# rev_n_v31.net
KiCad netlist of a schematic drawn in EAGLE
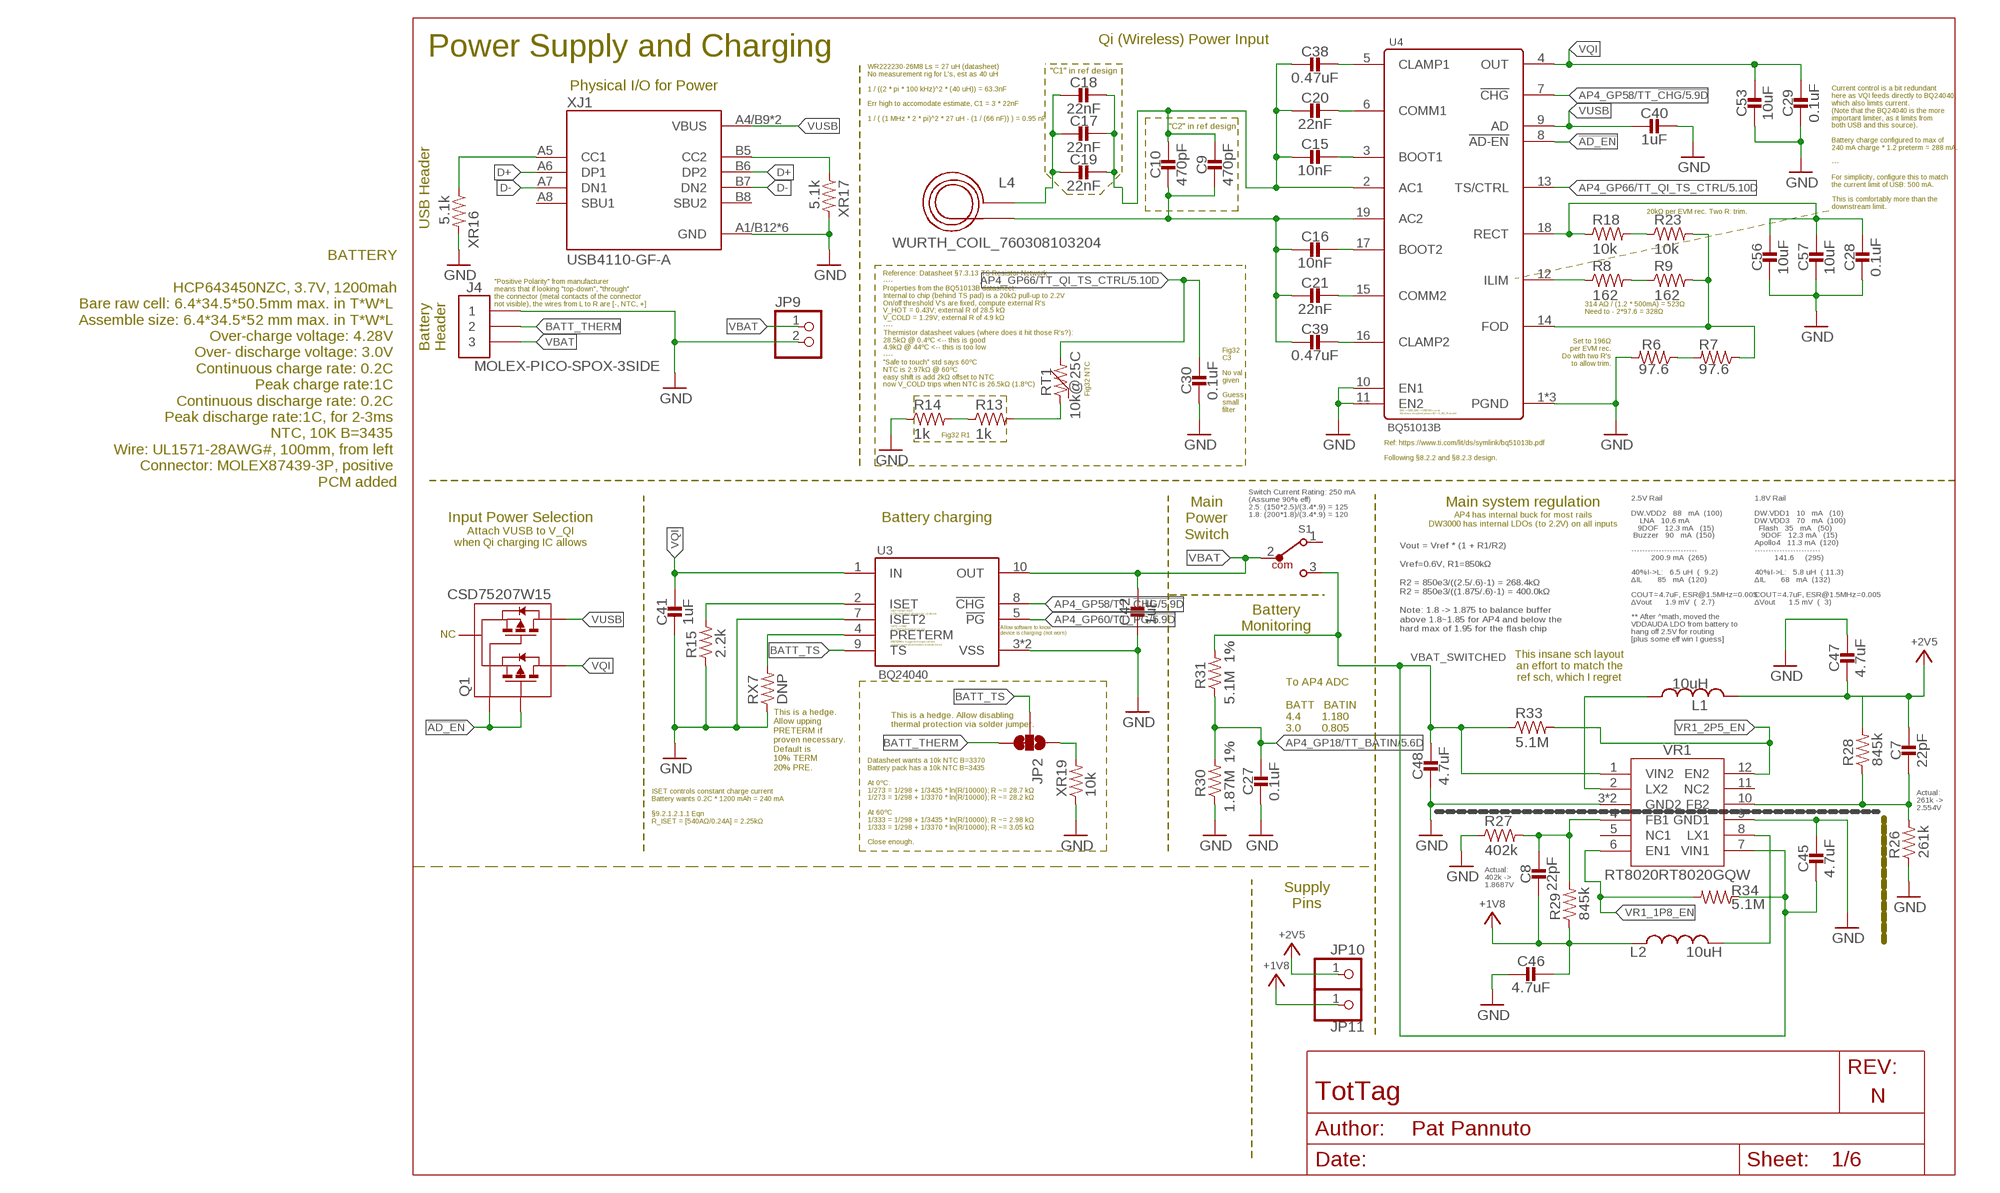
[diagram p0: schematic, sheet 1]
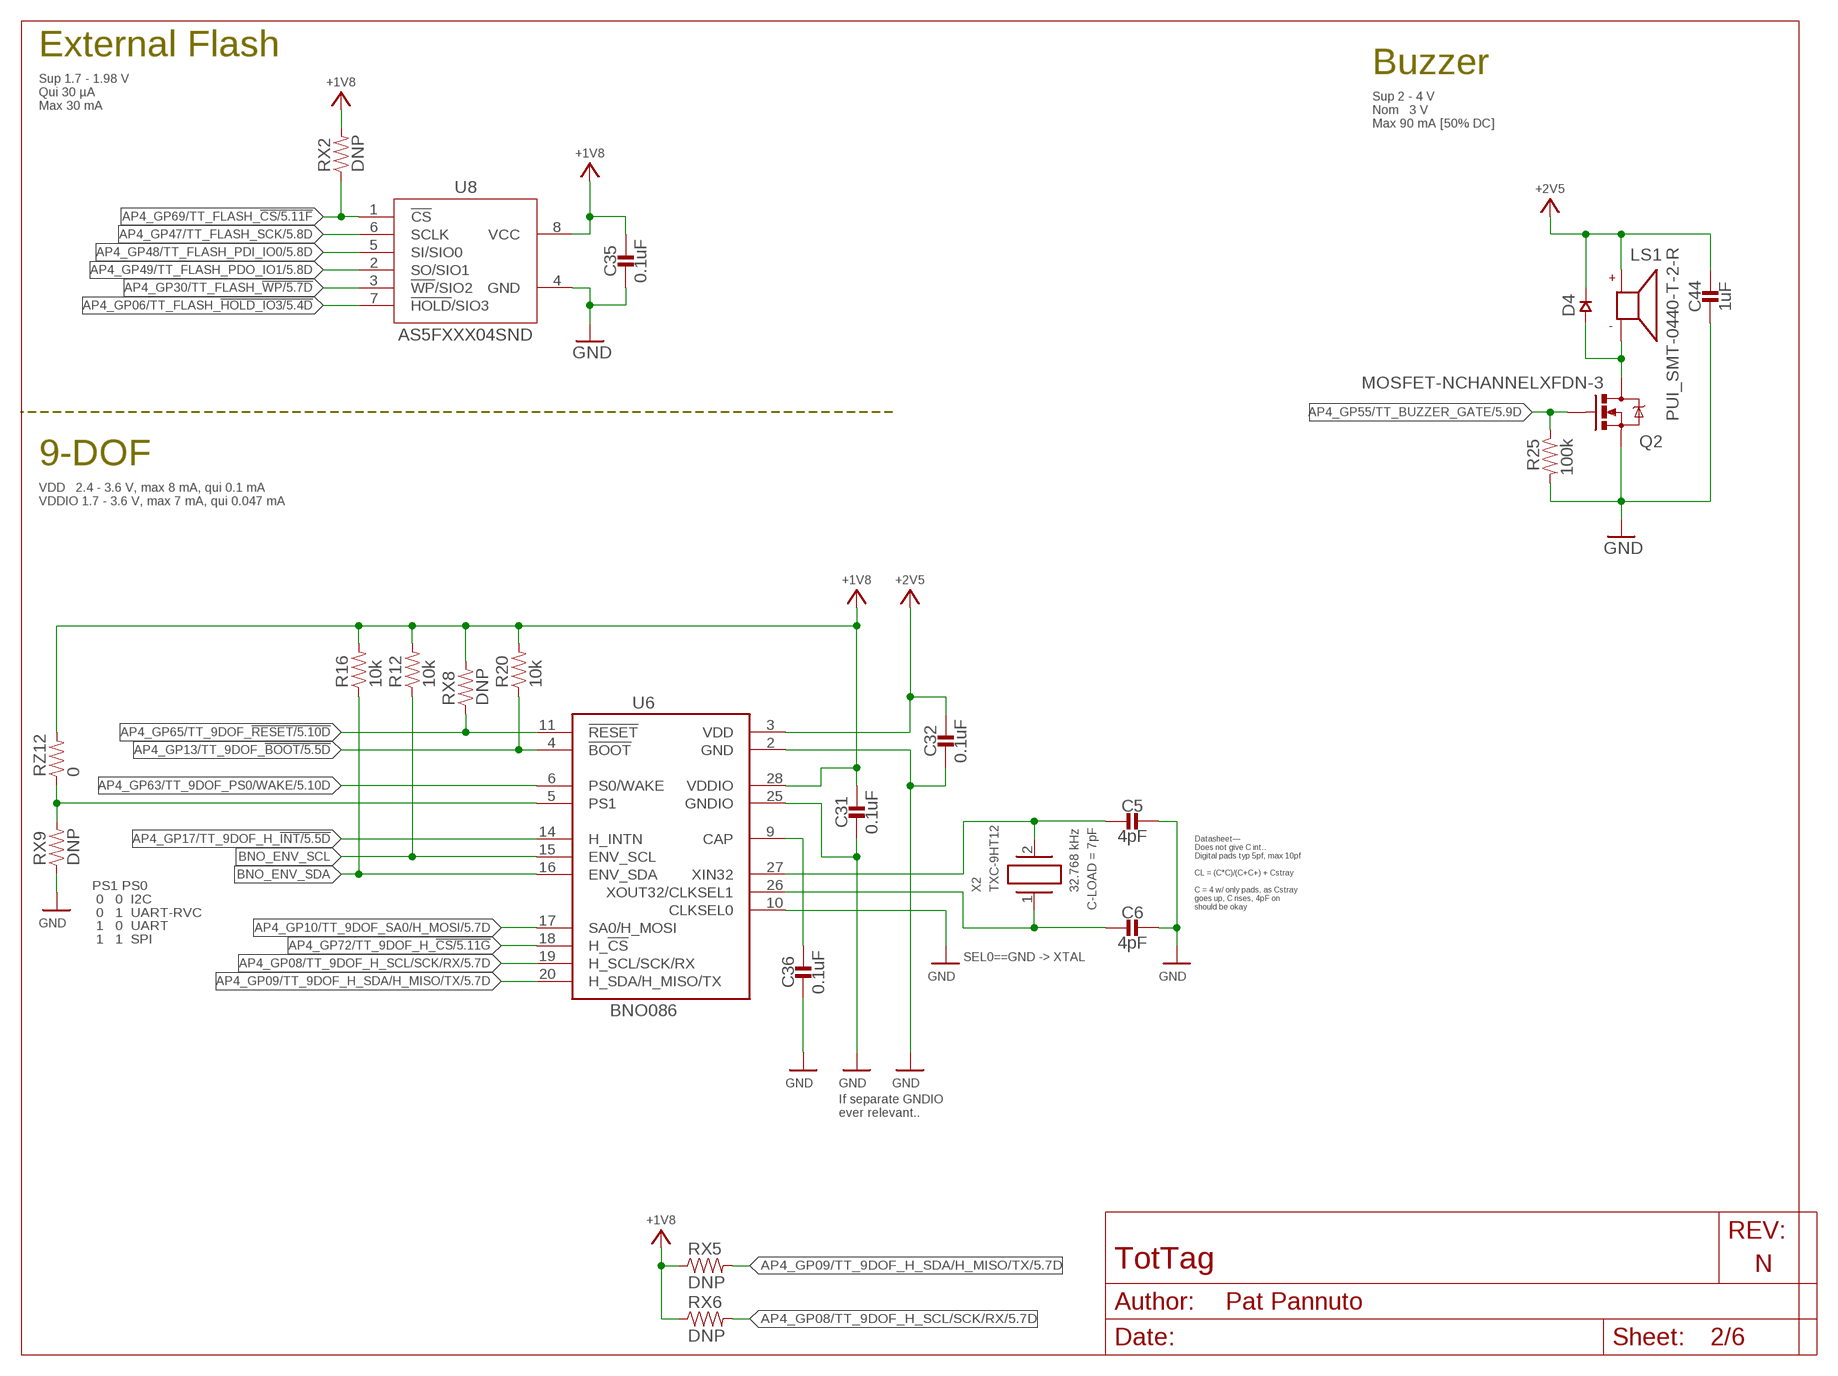
[diagram p1: schematic, sheet 2]
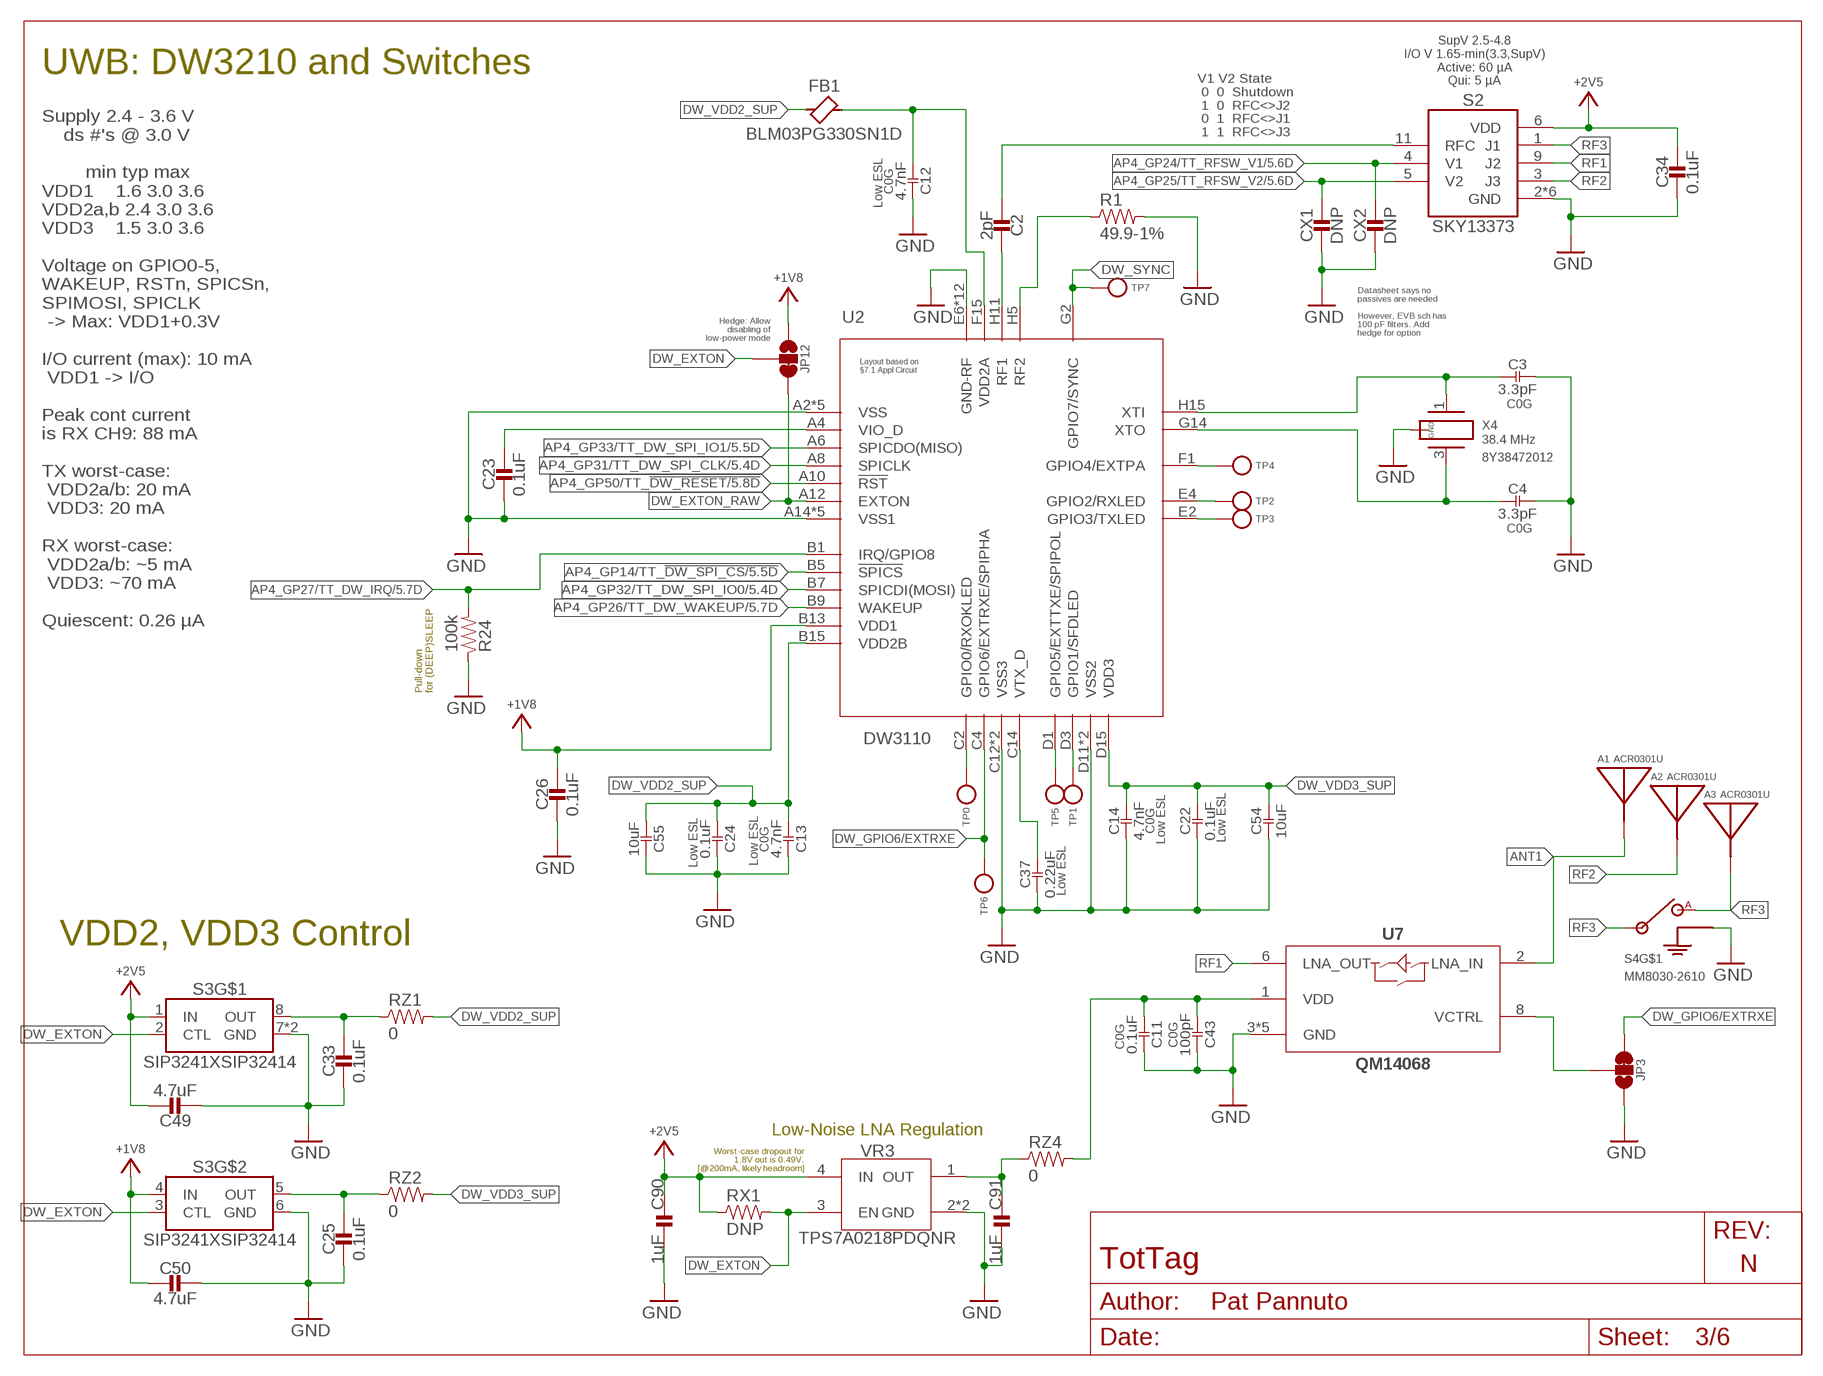
[diagram p2: schematic, sheet 3]
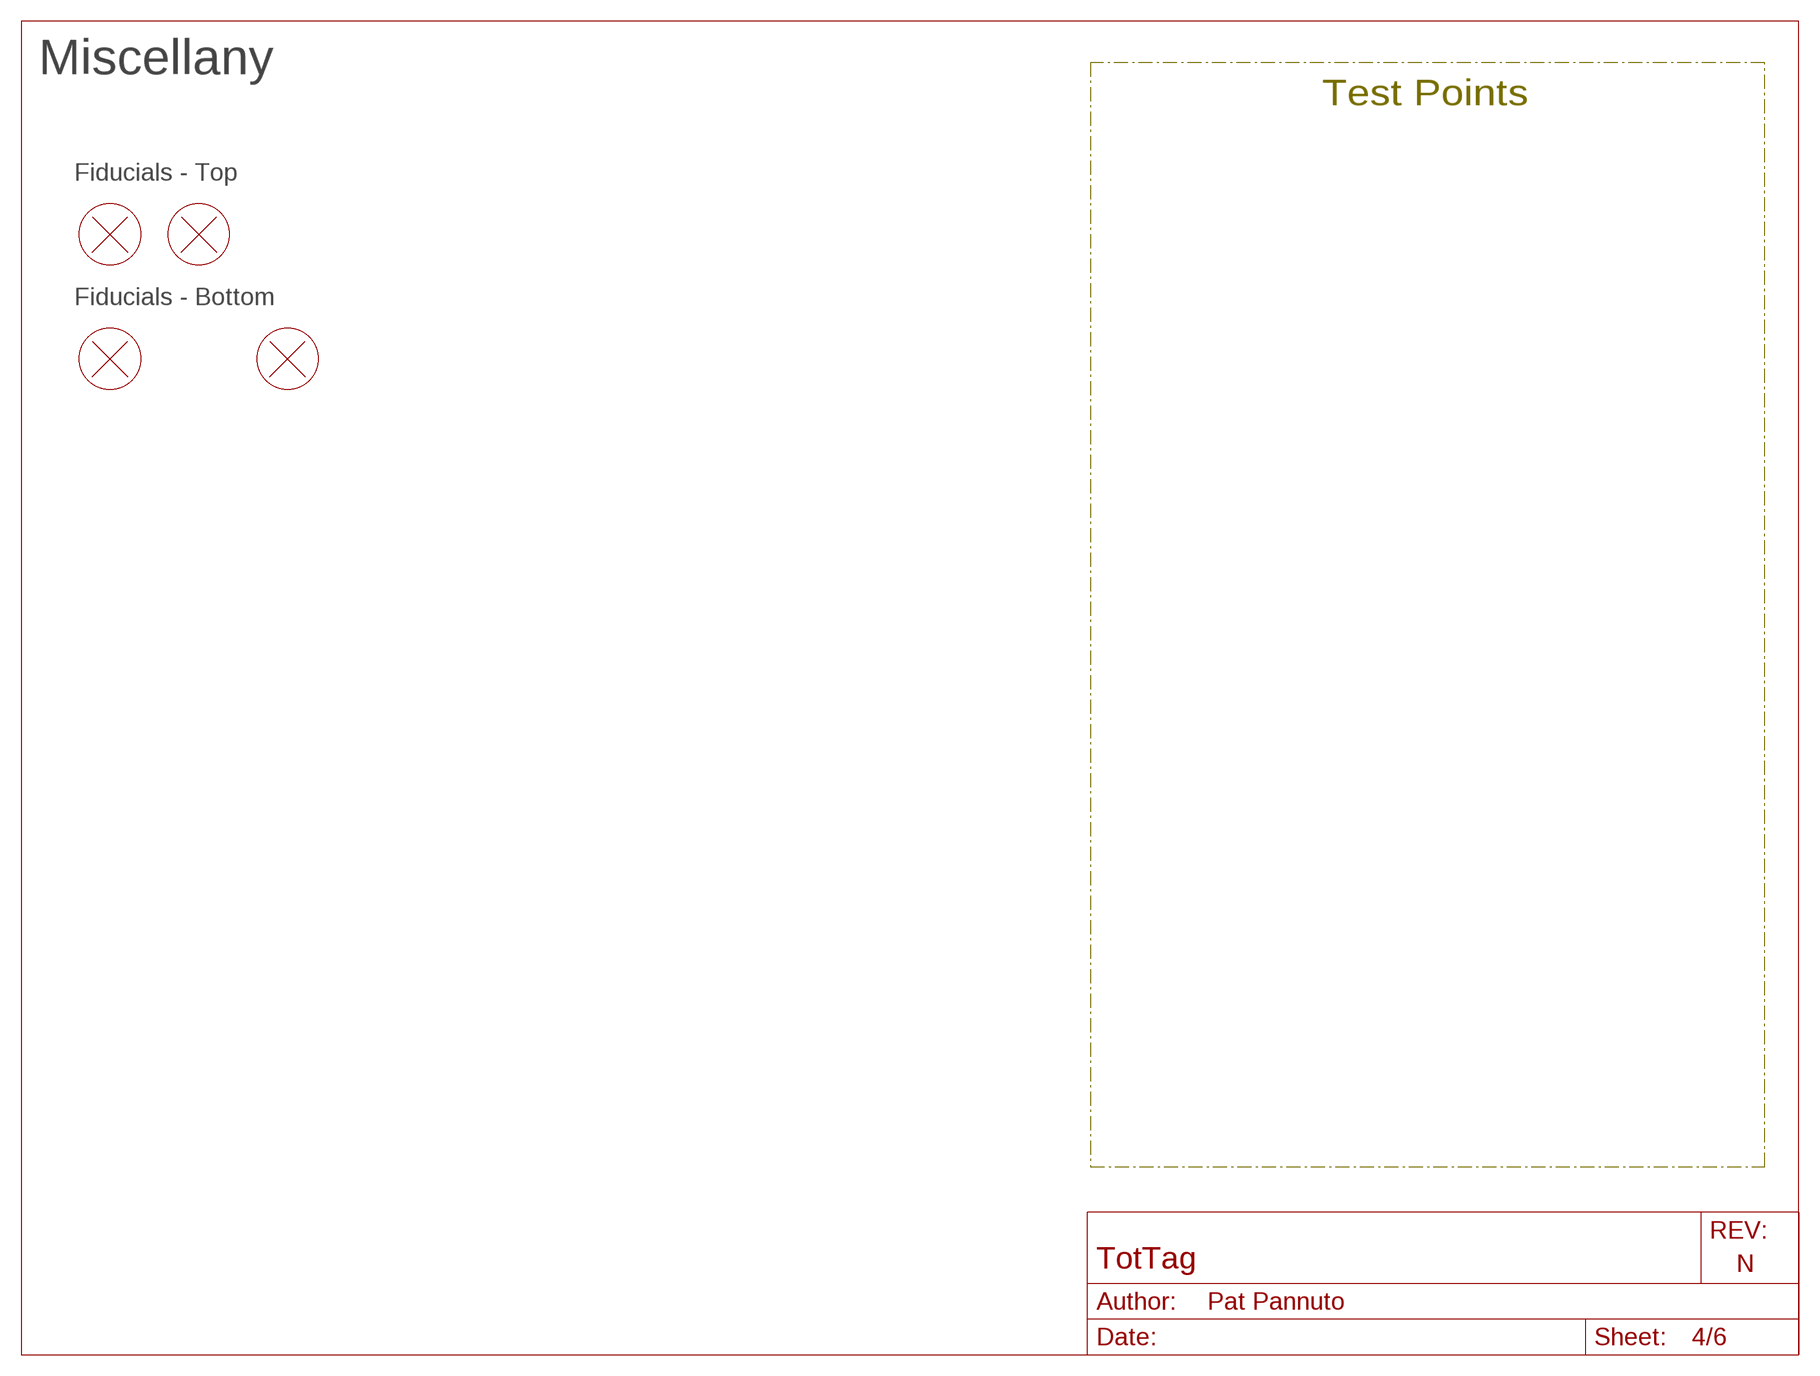
[diagram p3: schematic, sheet 4]
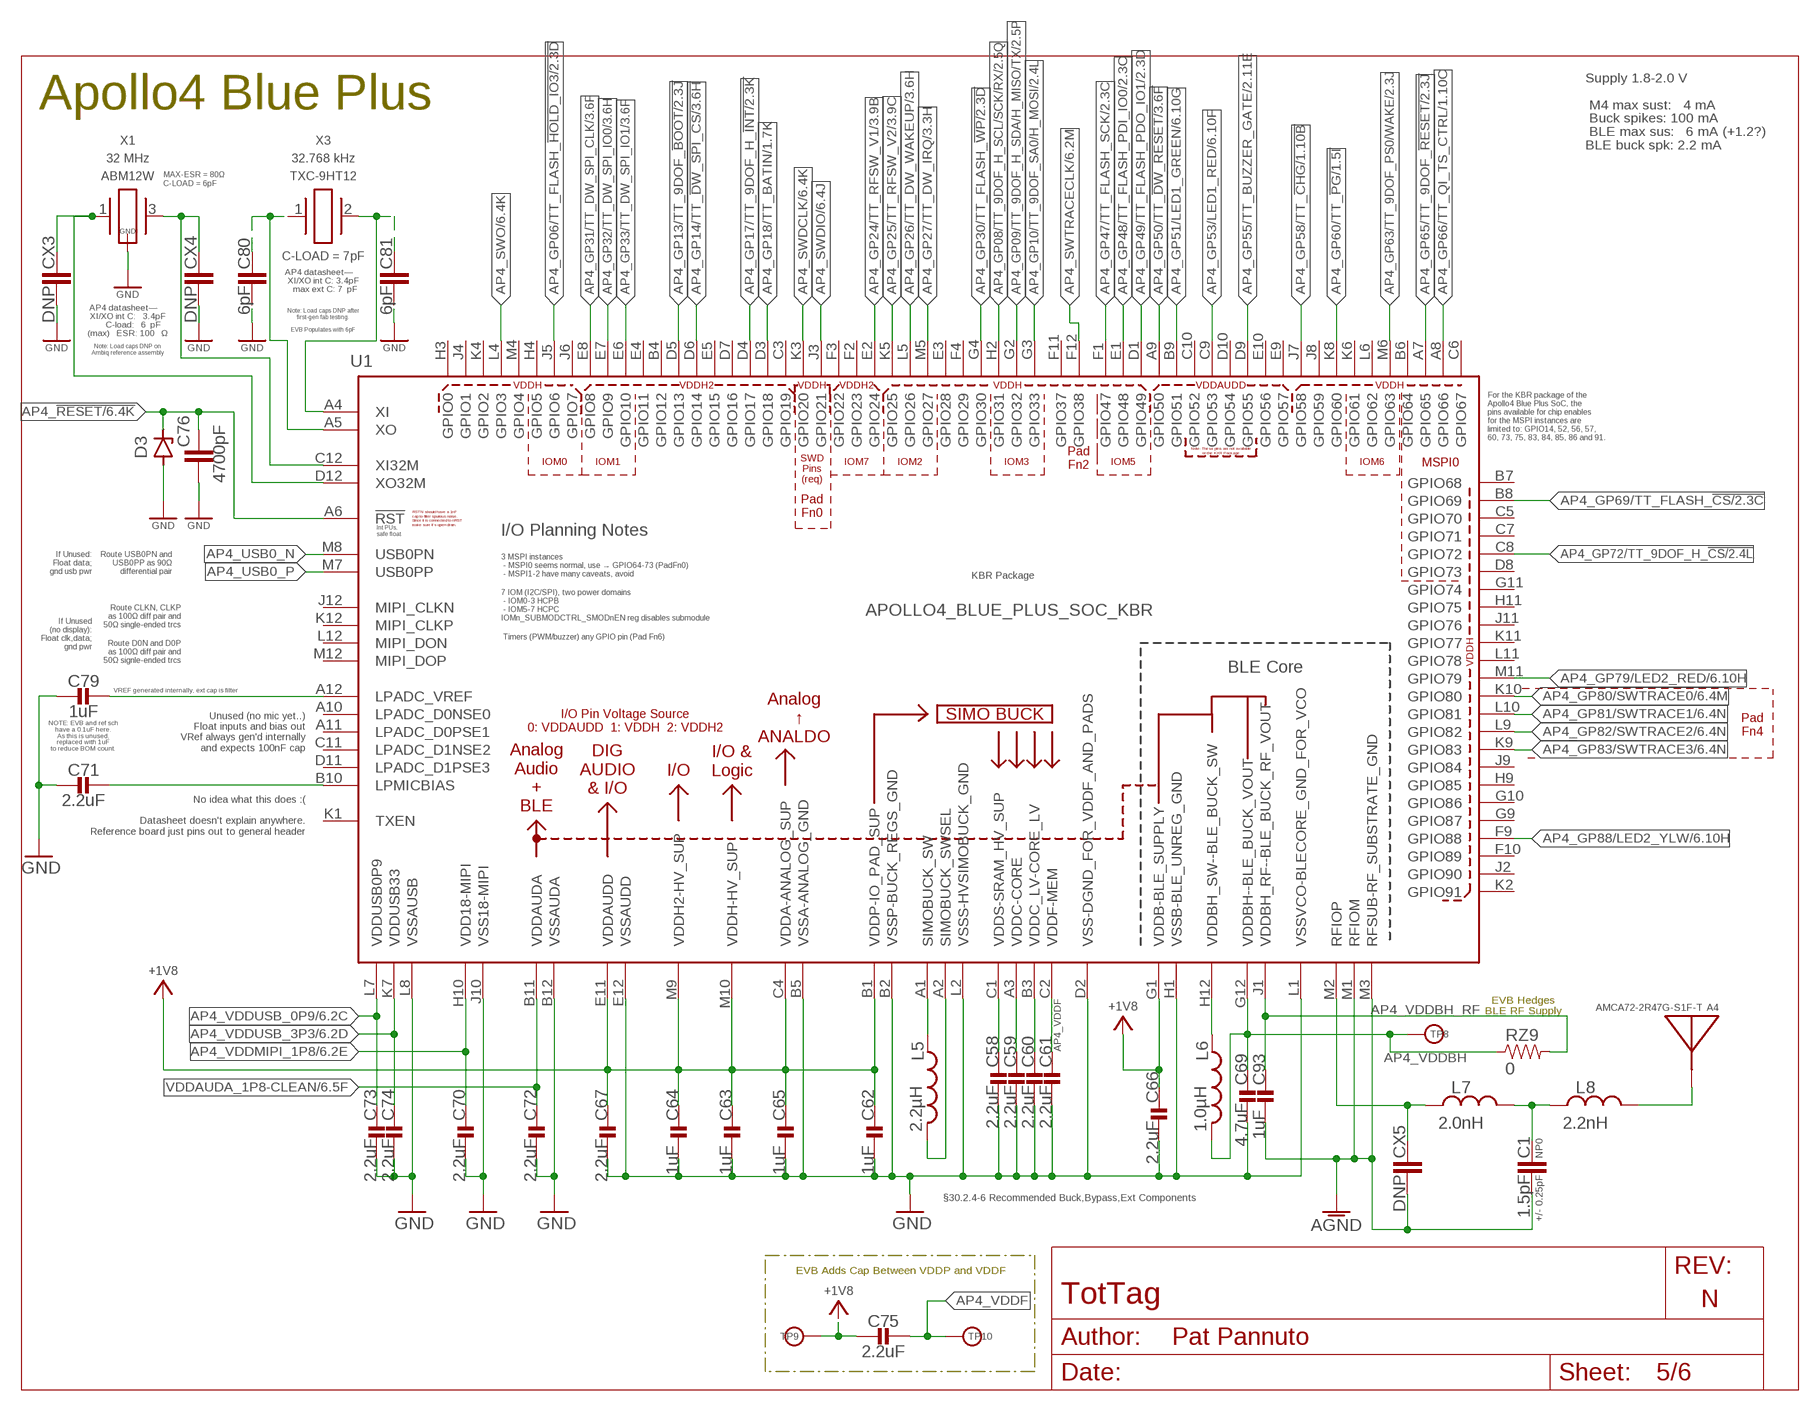
[diagram p4: schematic, sheet 5]
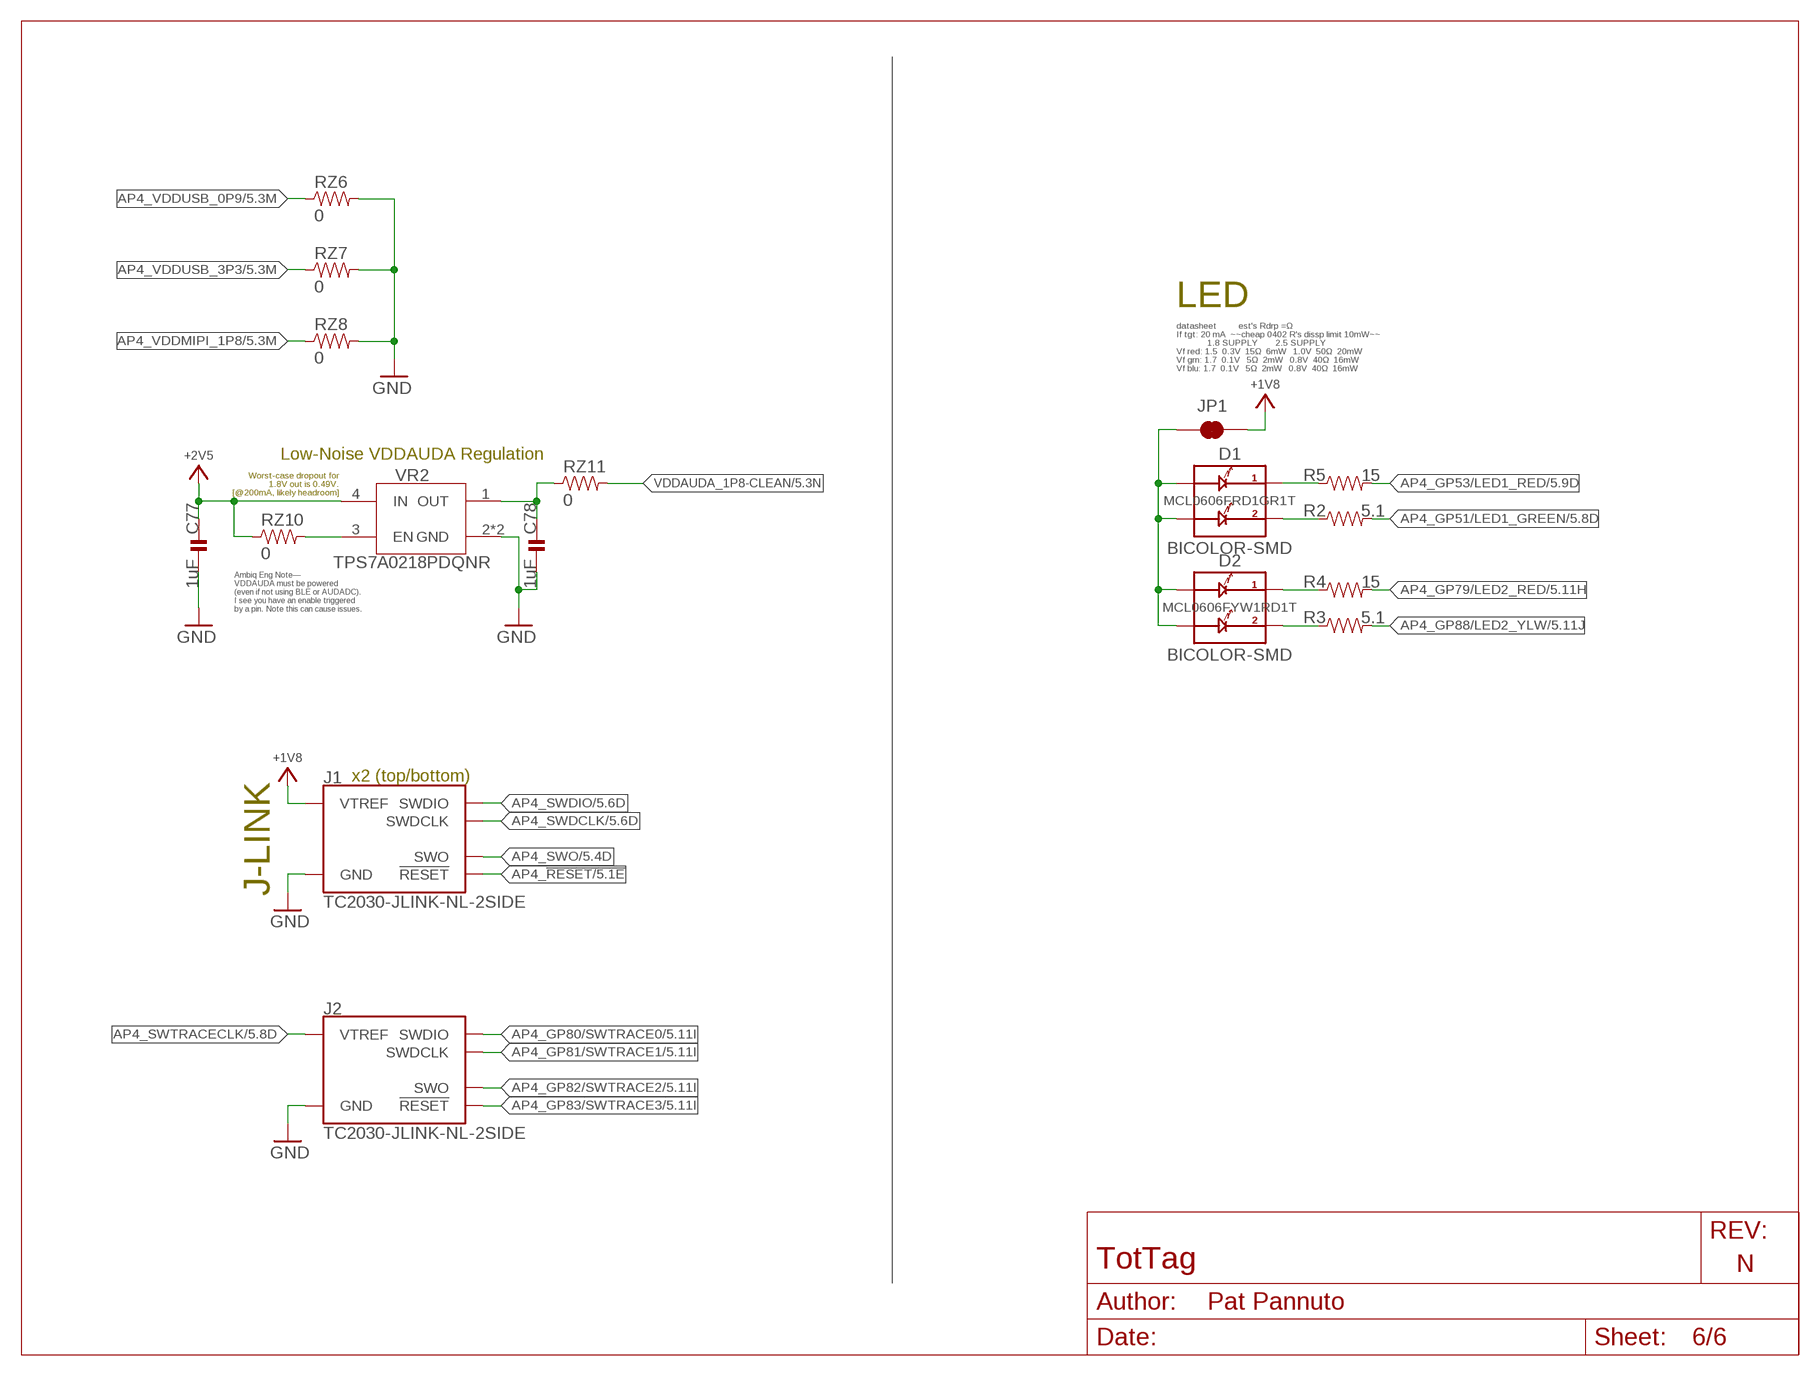
[diagram p5: schematic, sheet 6]

(export (version "E")
  (design (tool "Eeschema 10.0.6"))
  (components
    (comp (ref "A1")
      (value "ACR0301U")
      (footprint "eagle-import:ACR0301U")
      (fields (field (name "MANUFACTURER") "Abracon"))
      (libsource (lib "eagle-import") (part "ACR0301U"))
    )
    (comp (ref "A2")
      (value "ACR0301U")
      (footprint "eagle-import:ACR0301U")
      (fields (field (name "MANUFACTURER") "Abracon"))
      (libsource (lib "eagle-import") (part "ACR0301U"))
    )
    (comp (ref "A3")
      (value "ACR0301U")
      (footprint "eagle-import:ACR0301U")
      (fields (field (name "MANUFACTURER") "Abracon"))
      (libsource (lib "eagle-import") (part "ACR0301U"))
    )
    (comp (ref "C2")
      (value "2pF")
      (footprint "eagle-import:0201_CAP")
      (fields (field (name "MPN") "CBR02C209A5GAC"))
      (libsource (lib "eagle-import") (part "CAPACITOR0201_CAP"))
    )
    (comp (ref "C3")
      (value "3.3pF")
      (footprint "eagle-import:SMD_2012M-0805US-C")
      (fields
        (field (name "EIA") "C0G")
        (field (name "MANUFACTURER") "KYOCERA AVX")
        (field (name "MPN") "600F3R3BT250XT")
      )
      (libsource (lib "eagle-import") (part "C0805US"))
    )
    (comp (ref "C4")
      (value "3.3pF")
      (footprint "eagle-import:SMD_2012M-0805US-C")
      (fields
        (field (name "EIA") "C0G")
        (field (name "MANUFACTURER") "KYOCERA AVX")
        (field (name "MPN") "600F3R3BT250XT")
      )
      (libsource (lib "eagle-import") (part "C0805US"))
    )
    (comp (ref "C11")
      (value "0.1uF")
      (footprint "eagle-import:SMD_3216M-1206US-C")
      (fields (field (name "EIA") "C0G") (field (name "MPN") "GRM31C5C1H104JA01L"))
      (libsource (lib "eagle-import") (part "C1206US"))
    )
    (comp (ref "C12")
      (value "4.7nF")
      (footprint "eagle-import:SMD_1608M-0603US-C")
      (fields
        (field (name "EIA") "C0G")
        (field (name "FEATURES") "Low ESL")
        (field (name "MANUFACTURER") "KEMET")
        (field (name "MPN") "C0603C472J5GAC7867")
      )
      (libsource (lib "eagle-import") (part "C0603US"))
    )
    (comp (ref "C13")
      (value "4.7nF")
      (footprint "eagle-import:SMD_1608M-0603US-C")
      (fields
        (field (name "EIA") "C0G")
        (field (name "FEATURES") "Low ESL")
        (field (name "MANUFACTURER") "KEMET")
        (field (name "MPN") "C0603C472J5GAC7867")
      )
      (libsource (lib "eagle-import") (part "C0603US"))
    )
    (comp (ref "C14")
      (value "4.7nF")
      (footprint "eagle-import:SMD_1608M-0603US-C")
      (fields
        (field (name "EIA") "C0G")
        (field (name "FEATURES") "Low ESL")
        (field (name "MANUFACTURER") "KEMET")
        (field (name "MPN") "C0603C472J5GAC7867")
      )
      (libsource (lib "eagle-import") (part "C0603US"))
    )
    (comp (ref "C22")
      (value "0.1uF")
      (footprint "eagle-import:SMD_1608M-0603US-C")
      (fields (field (name "FEATURES") "Low ESL") (field (name "MPN") "C1608X7R1H104K080AA"))
      (libsource (lib "eagle-import") (part "C0603US"))
    )
    (comp (ref "C23")
      (value "0.1uF")
      (footprint "eagle-import:0402_CAP")
      (fields (field (name "MPN") "CL05A104KP5NNNC"))
      (libsource (lib "eagle-import") (part "passives_20904581_CAPACITOR0402_CAP"))
    )
    (comp (ref "C24")
      (value "0.1uF")
      (footprint "eagle-import:SMD_1608M-0603US-C")
      (fields (field (name "FEATURES") "Low ESL") (field (name "MPN") "C1608X7R1H104K080AA"))
      (libsource (lib "eagle-import") (part "C0603US"))
    )
    (comp (ref "C25")
      (value "0.1uF")
      (footprint "eagle-import:0402_CAP")
      (fields (field (name "MPN") "CL05A104KP5NNNC"))
      (libsource (lib "eagle-import") (part "passives_20904581_CAPACITOR0402_CAP"))
    )
    (comp (ref "C26")
      (value "0.1uF")
      (footprint "eagle-import:0402_CAP")
      (fields (field (name "MPN") "CL05A104KP5NNNC"))
      (libsource (lib "eagle-import") (part "passives_20904581_CAPACITOR0402_CAP"))
    )
    (comp (ref "C33")
      (value "0.1uF")
      (footprint "eagle-import:0402_CAP")
      (fields (field (name "MPN") "CL05A104KP5NNNC"))
      (libsource (lib "eagle-import") (part "passives_20904581_CAPACITOR0402_CAP"))
    )
    (comp (ref "C34")
      (value "0.1uF")
      (footprint "eagle-import:0402_CAP")
      (fields (field (name "MPN") "CL05A104KP5NNNC"))
      (libsource (lib "eagle-import") (part "passives_20904581_CAPACITOR0402_CAP"))
    )
    (comp (ref "C37")
      (value "0.22uF")
      (footprint "eagle-import:SMD_1608M-0603US-C")
      (fields (field (name "FEATURES") "Low ESL") (field (name "MPN") "C1608X7R1H224K080AB"))
      (libsource (lib "eagle-import") (part "C0603US"))
    )
    (comp (ref "C43")
      (value "100pF")
      (footprint "eagle-import:SMD_1005M-0402US-C")
      (fields (field (name "EIA") "C0G") (field (name "MPN") "C0402C101J3GACTU"))
      (libsource (lib "eagle-import") (part "C0402US"))
    )
    (comp (ref "C49")
      (value "4.7uF")
      (footprint "eagle-import:0603_CAP")
      (fields (field (name "MPN") "C1608X7S1A475K080AC"))
      (libsource (lib "eagle-import") (part "passives_20904581_CAPACITOR0603_CAP"))
    )
    (comp (ref "C50")
      (value "4.7uF")
      (footprint "eagle-import:0603_CAP")
      (fields (field (name "MPN") "C1608X7S1A475K080AC"))
      (libsource (lib "eagle-import") (part "passives_20904581_CAPACITOR0603_CAP"))
    )
    (comp (ref "C54")
      (value "10uF")
      (footprint "eagle-import:SMD_1608M-0603US-C")
      (fields (field (name "MPN") "CM105X5R106M25AT"))
      (libsource (lib "eagle-import") (part "C0603US"))
    )
    (comp (ref "C55")
      (value "10uF")
      (footprint "eagle-import:SMD_1608M-0603US-C")
      (fields (field (name "MPN") "CM105X5R106M25AT"))
      (libsource (lib "eagle-import") (part "C0603US"))
    )
    (comp (ref "C90")
      (value "1uF")
      (footprint "eagle-import:0201_CAP")
      (fields (field (name "MANUFACTURER") "Murata") (field (name "MPN") "GRM033R61A105ME44D"))
      (libsource (lib "eagle-import") (part "passives_20904581_CAPACITOR0201_CAP"))
    )
    (comp (ref "C91")
      (value "1uF")
      (footprint "eagle-import:0201_CAP")
      (fields (field (name "MANUFACTURER") "Murata") (field (name "MPN") "GRM033R61A105ME44D"))
      (libsource (lib "eagle-import") (part "passives_20904581_CAPACITOR0201_CAP"))
    )
    (comp (ref "CX1")
      (value "DNP")
      (footprint "eagle-import:0603_CAP")
      (libsource (lib "eagle-import") (part "passives_20904581_CAPACITOR0603_CAP"))
    )
    (comp (ref "CX2")
      (value "DNP")
      (footprint "eagle-import:0603_CAP")
      (libsource (lib "eagle-import") (part "passives_20904581_CAPACITOR0603_CAP"))
    )
    (comp (ref "FB1")
      (value "BLM03PG330SN1D")
      (footprint "eagle-import:0201_FB")
      (fields (field (name "MANUFACTURER") "Murata"))
      (libsource (lib "eagle-import") (part "FERRITE_BEAD0201"))
    )
    (comp (ref "JP3")
      (value "JUMPER-SMT_3_1-NC_TRACE_SILK")
      (footprint "eagle-import:SMT-JUMPER_3_1-NC_TRACE_SILK")
      (libsource (lib "eagle-import") (part "JUMPER-SMT_3_1-NC_TRACE_SILK"))
    )
    (comp (ref "JP12")
      (value "JUMPER-SMT_3_1-NC_TRACE_SILK")
      (footprint "eagle-import:SMT-JUMPER_3_1-NC_TRACE_SILK")
      (libsource (lib "eagle-import") (part "JUMPER-SMT_3_1-NC_TRACE_SILK"))
    )
    (comp (ref "R1")
      (value "49.9-1%")
      (footprint "eagle-import:0201_RES")
      (fields (field (name "MPN") "ERJ-1GNF49R9C"))
      (libsource (lib "eagle-import") (part "passives_20904581_RESISTOR0201_RES"))
    )
    (comp (ref "R24")
      (value "100k")
      (footprint "eagle-import:0402_RES")
      (fields (field (name "MPN") "RT0402BRE07100KL"))
      (libsource (lib "eagle-import") (part "RESISTOR0402_RES"))
    )
    (comp (ref "RX1")
      (value "DNP")
      (footprint "eagle-import:0603-RES")
      (libsource (lib "eagle-import") (part "passives_20904581_RESISTOR0603_RES"))
    )
    (comp (ref "RZ1")
      (value "0")
      (footprint "eagle-import:0603-RES")
      (fields (field (name "MPN") "RMCF0603ZT0R00"))
      (libsource (lib "eagle-import") (part "passives_20904581_RESISTOR0603_RES"))
    )
    (comp (ref "RZ2")
      (value "0")
      (footprint "eagle-import:0603-RES")
      (fields (field (name "MPN") "RMCF0603ZT0R00"))
      (libsource (lib "eagle-import") (part "passives_20904581_RESISTOR0603_RES"))
    )
    (comp (ref "RZ4")
      (value "0")
      (footprint "eagle-import:0402_RES")
      (fields (field (name "MPN") "RMCF0402ZT0R00"))
      (libsource (lib "eagle-import") (part "passives_20904581_RESISTOR0402_RES"))
    )
    (comp (ref "S2")
      (value "SKY13373")
      (footprint "eagle-import:SKY13373")
      (fields (field (name "MANUFACTURER") "Skyworks") (field (name "MPN") "SKY13373-460LF"))
      (libsource (lib "eagle-import") (part "SKY13373"))
    )
    (comp (ref "S3")
      (value "SIP3241XSIP32414")
      (footprint "eagle-import:TDFN2X2X0P6-8")
      (fields (field (name "MANUFACTURER") "Vishay") (field (name "MPN") "SIP32414DNP-T1-GE4"))
      (libsource (lib "eagle-import") (part "SIP3241XSIP32414"))
    )
    (comp (ref "S4")
      (value "MM8030-2610")
      (footprint "eagle-import:MM8030-2610")
      (fields (field (name "MANUFACTURER") "Murata"))
      (libsource (lib "eagle-import") (part "MM8030-2610"))
    )
    (comp (ref "TP0")
      (value "TEST-POINT")
      (footprint "eagle-import:PAD.03X.03")
      (libsource (lib "eagle-import") (part "TEST-POINT"))
    )
    (comp (ref "TP1")
      (value "TEST-POINT")
      (footprint "eagle-import:PAD.03X.03")
      (libsource (lib "eagle-import") (part "TEST-POINT"))
    )
    (comp (ref "TP2")
      (value "TEST-POINT")
      (footprint "eagle-import:PAD.03X.03")
      (libsource (lib "eagle-import") (part "TEST-POINT"))
    )
    (comp (ref "TP3")
      (value "TEST-POINT")
      (footprint "eagle-import:PAD.03X.03")
      (libsource (lib "eagle-import") (part "TEST-POINT"))
    )
    (comp (ref "TP4")
      (value "TEST-POINT")
      (footprint "eagle-import:PAD.03X.03")
      (libsource (lib "eagle-import") (part "TEST-POINT"))
    )
    (comp (ref "TP5")
      (value "TEST-POINT")
      (footprint "eagle-import:PAD.03X.03")
      (libsource (lib "eagle-import") (part "TEST-POINT"))
    )
    (comp (ref "TP6")
      (value "TEST-POINT")
      (footprint "eagle-import:PAD.03X.03")
      (libsource (lib "eagle-import") (part "TEST-POINT"))
    )
    (comp (ref "TP7")
      (value "TEST-POINT")
      (footprint "eagle-import:PAD.03X.03")
      (libsource (lib "eagle-import") (part "TEST-POINT"))
    )
    (comp (ref "U2")
      (value "DW3110")
      (footprint "eagle-import:WLCSP52")
      (fields (field (name "MANUFACTURER") "Qorvo"))
      (libsource (lib "eagle-import") (part "DW3110"))
    )
    (comp (ref "U7")
      (value "QM14068")
      (footprint "eagle-import:QM14068")
      (fields (field (name "MANUFACTURER") "Qorvo"))
      (libsource (lib "eagle-import") (part "QM14068"))
    )
    (comp (ref "VR3")
      (value "TPS7A0218PDQNR")
      (footprint "eagle-import:4-XDFN-EP")
      (libsource (lib "eagle-import") (part "TPS7A0218PDQNR"))
    )
    (comp (ref "X4")
      (value "TXC-8Y")
      (footprint "eagle-import:TXC-8Y")
      (fields
        (field (name "FREQ") "38.4 MHz")
        (field (name "MANUFACTURER") "TXC")
        (field (name "MPN") "8Y38472012")
      )
      (libsource (lib "eagle-import") (part "TXC-8Y"))
    )
    (comp (ref "A4")
      (value "AMCA72-2R47G-S1F-T")
      (footprint "eagle-import:AMCA72-2R470G-S1F-T")
      (fields (field (name "MPN") "AMCA72-2R470G-S1F-T4"))
      (libsource (lib "eagle-import") (part "AMCA72-2R47G-S1F-T"))
    )
    (comp (ref "C1")
      (value "1.5pF")
      (footprint "eagle-import:CAPC1005X60")
      (description "CAP CER 1.5PF 50V C0G/NP0 0402")
      (fields
        (field (name "MANUFACTURER") "KEMET")
        (field (name "MPN") "C0402C159C5GACTU")
        (field (name "TEMPCOEFF") "NP0")
        (field (name "TOLERANCE") "+/- 0.25pF")
      )
      (libsource (lib "eagle-import") (part "CCHIP-0402(1005-METRIC)_"))
    )
    (comp (ref "C58")
      (value "2.2uF")
      (footprint "eagle-import:0201_CAP")
      (fields (field (name "MANUFACTURER") "Murata") (field (name "MPN") "GRM033R61A225KE47D"))
      (libsource (lib "eagle-import") (part "passives_20904581_CAPACITOR0201_CAP"))
    )
    (comp (ref "C59")
      (value "2.2uF")
      (footprint "eagle-import:0201_CAP")
      (fields (field (name "MANUFACTURER") "Murata") (field (name "MPN") "GRM033R61A225KE47D"))
      (libsource (lib "eagle-import") (part "passives_20904581_CAPACITOR0201_CAP"))
    )
    (comp (ref "C60")
      (value "2.2uF")
      (footprint "eagle-import:0201_CAP")
      (fields (field (name "MANUFACTURER") "Murata") (field (name "MPN") "GRM033R61A225KE47D"))
      (libsource (lib "eagle-import") (part "passives_20904581_CAPACITOR0201_CAP"))
    )
    (comp (ref "C61")
      (value "2.2uF")
      (footprint "eagle-import:0201_CAP")
      (fields (field (name "MANUFACTURER") "Murata") (field (name "MPN") "GRM033R61A225KE47D"))
      (libsource (lib "eagle-import") (part "passives_20904581_CAPACITOR0201_CAP"))
    )
    (comp (ref "C62")
      (value "1uF")
      (footprint "eagle-import:0201_CAP")
      (fields (field (name "MANUFACTURER") "Murata") (field (name "MPN") "GRM033R61A105ME44D"))
      (libsource (lib "eagle-import") (part "passives_20904581_CAPACITOR0201_CAP"))
    )
    (comp (ref "C63")
      (value "1uF")
      (footprint "eagle-import:0201_CAP")
      (fields (field (name "MANUFACTURER") "Murata") (field (name "MPN") "GRM033R61A105ME44D"))
      (libsource (lib "eagle-import") (part "passives_20904581_CAPACITOR0201_CAP"))
    )
    (comp (ref "C64")
      (value "1uF")
      (footprint "eagle-import:0201_CAP")
      (fields (field (name "MANUFACTURER") "Murata") (field (name "MPN") "GRM033R61A105ME44D"))
      (libsource (lib "eagle-import") (part "passives_20904581_CAPACITOR0201_CAP"))
    )
    (comp (ref "C65")
      (value "1uF")
      (footprint "eagle-import:0201_CAP")
      (fields (field (name "MANUFACTURER") "Murata") (field (name "MPN") "GRM033R61A105ME44D"))
      (libsource (lib "eagle-import") (part "passives_20904581_CAPACITOR0201_CAP"))
    )
    (comp (ref "C66")
      (value "2.2uF")
      (footprint "eagle-import:0201_CAP")
      (fields (field (name "MANUFACTURER") "Murata") (field (name "MPN") "GRM033R61A225KE47D"))
      (libsource (lib "eagle-import") (part "passives_20904581_CAPACITOR0201_CAP"))
    )
    (comp (ref "C67")
      (value "2.2uF")
      (footprint "eagle-import:0201_CAP")
      (fields (field (name "MANUFACTURER") "Murata") (field (name "MPN") "GRM033R61A225KE47D"))
      (libsource (lib "eagle-import") (part "passives_20904581_CAPACITOR0201_CAP"))
    )
    (comp (ref "C69")
      (value "4.7uF")
      (footprint "eagle-import:0402_CAP")
      (fields (field (name "MPN") "CL05A475MP5NRNC"))
      (libsource (lib "eagle-import") (part "CAPACITOR0402_CAP"))
    )
    (comp (ref "C70")
      (value "2.2uF")
      (footprint "eagle-import:0201_CAP")
      (fields (field (name "MANUFACTURER") "Murata") (field (name "MPN") "GRM033R61A225KE47D"))
      (libsource (lib "eagle-import") (part "passives_20904581_CAPACITOR0201_CAP"))
    )
    (comp (ref "C71")
      (value "2.2uF")
      (footprint "eagle-import:0201_CAP")
      (fields (field (name "MANUFACTURER") "Murata") (field (name "MPN") "GRM033R61A225KE47D"))
      (libsource (lib "eagle-import") (part "passives_20904581_CAPACITOR0201_CAP"))
    )
    (comp (ref "C72")
      (value "2.2uF")
      (footprint "eagle-import:0201_CAP")
      (fields (field (name "MANUFACTURER") "Murata") (field (name "MPN") "GRM033R61A225KE47D"))
      (libsource (lib "eagle-import") (part "passives_20904581_CAPACITOR0201_CAP"))
    )
    (comp (ref "C73")
      (value "2.2uF")
      (footprint "eagle-import:0201_CAP")
      (fields (field (name "MANUFACTURER") "Murata") (field (name "MPN") "GRM033R61A225KE47D"))
      (libsource (lib "eagle-import") (part "passives_20904581_CAPACITOR0201_CAP"))
    )
    (comp (ref "C74")
      (value "2.2uF")
      (footprint "eagle-import:0201_CAP")
      (fields (field (name "MANUFACTURER") "Murata") (field (name "MPN") "GRM033R61A225KE47D"))
      (libsource (lib "eagle-import") (part "passives_20904581_CAPACITOR0201_CAP"))
    )
    (comp (ref "C75")
      (value "2.2uF")
      (footprint "eagle-import:0201_CAP")
      (fields (field (name "MANUFACTURER") "Murata") (field (name "MPN") "GRM033R61A225KE47D"))
      (libsource (lib "eagle-import") (part "passives_20904581_CAPACITOR0201_CAP"))
    )
    (comp (ref "C76")
      (value "4700pF")
      (footprint "eagle-import:CAPC1005X60")
      (fields (field (name "MPN") "KGM05AR71E472KH"))
      (libsource (lib "eagle-import") (part "CCHIP-0402(1005-METRIC)_"))
    )
    (comp (ref "C79")
      (value "1uF")
      (footprint "eagle-import:0201_CAP")
      (fields (field (name "MANUFACTURER") "MURATA") (field (name "MPN") "GRM033R61A105ME44D"))
      (libsource (lib "eagle-import") (part "passives_20904581_CAPACITOR0201_CAP"))
    )
    (comp (ref "C80")
      (value "6pF")
      (footprint "eagle-import:CAPC1005X60")
      (fields (field (name "MANUFACTURER") "Murata") (field (name "MPN") "GCM1555C1H6R0BA16D"))
      (libsource (lib "eagle-import") (part "CCHIP-0402(1005-METRIC)_"))
    )
    (comp (ref "C81")
      (value "6pF")
      (footprint "eagle-import:CAPC1005X60")
      (fields (field (name "MANUFACTURER") "Murata") (field (name "MPN") "GCM1555C1H6R0BA16D"))
      (libsource (lib "eagle-import") (part "CCHIP-0402(1005-METRIC)_"))
    )
    (comp (ref "C93")
      (value "1uF")
      (footprint "eagle-import:0201_CAP")
      (fields (field (name "MANUFACTURER") "Murata") (field (name "MPN") "GRM033R61A105ME44D"))
      (libsource (lib "eagle-import") (part "passives_20904581_CAPACITOR0201_CAP"))
    )
    (comp (ref "CX3")
      (value "DNP")
      (footprint "eagle-import:CAPC1005X60")
      (libsource (lib "eagle-import") (part "CCHIP-0402(1005-METRIC)_"))
    )
    (comp (ref "CX4")
      (value "DNP")
      (footprint "eagle-import:CAPC1005X60")
      (libsource (lib "eagle-import") (part "CCHIP-0402(1005-METRIC)_"))
    )
    (comp (ref "CX5")
      (value "DNP")
      (footprint "eagle-import:CAPC1005X60")
      (libsource (lib "eagle-import") (part "CCHIP-0402(1005-METRIC)_"))
    )
    (comp (ref "D3")
      (value "ZENER")
      (footprint "eagle-import:SODFL1608X70")
      (description "DIODE TVS 5.5V STANDOFF 8V BREAKDOWN SC79")
      (fields (field (name "MANUFACTURER") "NXP SEMICONDUCTOR") (field (name "MPN") "PESD5V0X1UB,135"))
      (libsource (lib "eagle-import") (part "ZENERSODFL(1608-METRIC)_"))
    )
    (comp (ref "L5")
      (value "2.2µH")
      (footprint "eagle-import:0805_CAP")
      (fields (field (name "MANUFACTURER") "Murata") (field (name "MPN") "DFE201210U-2R2M=P2"))
      (libsource (lib "eagle-import") (part "INDUCTOR0805"))
    )
    (comp (ref "L6")
      (value "1.0µH")
      (footprint "eagle-import:0603_CAP")
      (fields (field (name "MANUFACTURER") "Murata") (field (name "MPN") "DFE18SAN1R0ME0L"))
      (libsource (lib "eagle-import") (part "INDUCTOR0603"))
    )
    (comp (ref "L7")
      (value "2.0nH")
      (footprint "eagle-import:INDC1006X60N")
      (description "FIXED IND 2.0NH0.1NH SMD")
      (fields
        (field (name "MANUFACTURER") "Murata")
        (field (name "MPN") "LQG15HS2N0B02D")
        (field (name "TOLERANCE") "+/- 0.1 nH")
      )
      (libsource (lib "eagle-import") (part "LCHIP-0402(1006-METRIC)_"))
    )
    (comp (ref "L8")
      (value "2.2nH")
      (footprint "eagle-import:INDC1006X60N")
      (description "FIXED IND 2.2NH0.1NH SMD")
      (fields
        (field (name "MANUFACTURER") "Murata")
        (field (name "MPN") "LQG15HN2N2B02D")
        (field (name "TOLERANCE") "+/- 0.1 nH")
      )
      (libsource (lib "eagle-import") (part "LCHIP-0402(1006-METRIC)_"))
    )
    (comp (ref "RZ9")
      (value "0")
      (footprint "eagle-import:0402_RES")
      (fields (field (name "MPN") "RMCF0402ZT0R00"))
      (libsource (lib "eagle-import") (part "passives_20904581_RESISTOR0402_RES"))
    )
    (comp (ref "TP8")
      (value "VDDBH")
      (footprint "eagle-import:PAD.03X.03")
      (libsource (lib "eagle-import") (part "TEST-POINT"))
    )
    (comp (ref "TP9")
      (value "VDDP")
      (footprint "eagle-import:PAD.03X.03")
      (libsource (lib "eagle-import") (part "TEST-POINT"))
    )
    (comp (ref "TP10")
      (value "VDDF")
      (footprint "eagle-import:PAD.03X.03")
      (libsource (lib "eagle-import") (part "TEST-POINT"))
    )
    (comp (ref "U1")
      (value "APOLLO4_BLUE_PLUS_SOC_KBR")
      (footprint "eagle-import:APOLLO4_BLUE_SOC_BGA")
      (fields (field (name "MANUFACTURER") "Ambiq") (field (name "MPN") "AMA4B2KP-KBR"))
      (libsource (lib "eagle-import") (part "APOLLO4_BLUE_PLUS_SOC_KBR"))
    )
    (comp (ref "X1")
      (value "ABM12W")
      (footprint "eagle-import:ABM12W")
      (fields
        (field (name "C-LOAD") "6pF")
        (field (name "FREQUENCY") "32 MHz")
        (field (name "MANUFACTURER") "Abracon")
        (field (name "MAX-ESR") "80Ω")
        (field (name "MPN") "ABM12W-32.0000MHZ-6-D1X-T3")
      )
      (libsource (lib "eagle-import") (part "ABM12W"))
    )
    (comp (ref "X3")
      (value "TXC-9HT12")
      (footprint "eagle-import:TXC-9HT12")
      (fields
        (field (name "C-LOAD") "7pF")
        (field (name "FREQUENCY") "32.768 kHz")
        (field (name "MANUFACTURER") "TXC Corp")
        (field (name "MPN") "9HT12-32.768KDZY-T")
      )
      (libsource (lib "eagle-import") (part "TXC-9HT12"))
    )
    (comp (ref "C77")
      (value "1uF")
      (footprint "eagle-import:0201_CAP")
      (fields (field (name "MANUFACTURER") "Murata") (field (name "MPN") "GRM033R61A105ME44D"))
      (libsource (lib "eagle-import") (part "passives_20904581_CAPACITOR0201_CAP"))
    )
    (comp (ref "C78")
      (value "1uF")
      (footprint "eagle-import:0201_CAP")
      (fields (field (name "MANUFACTURER") "Murata") (field (name "MPN") "GRM033R61A105ME44D"))
      (libsource (lib "eagle-import") (part "passives_20904581_CAPACITOR0201_CAP"))
    )
    (comp (ref "D1")
      (value "BICOLOR-SMD")
      (footprint "eagle-import:LED-0606")
      (fields (field (name "MPN") "MCL0606FRD1GR1T"))
      (libsource (lib "eagle-import") (part "BICOLOR-SMD"))
    )
    (comp (ref "D2")
      (value "BICOLOR-SMD")
      (footprint "eagle-import:LED-0606")
      (fields (field (name "MPN") "MCL0606FYW1RD1T"))
      (libsource (lib "eagle-import") (part "BICOLOR-SMD"))
    )
    (comp (ref "J1")
      (value "TC2030-JLINK-NL-2SIDE")
      (footprint "eagle-import:TC2030-IDC-NL-2SIDE")
      (libsource (lib "eagle-import") (part "TC2030-JLINK-NL-2SIDE"))
    )
    (comp (ref "J2")
      (value "TC2030-JLINK-NL-2SIDE")
      (footprint "eagle-import:TC2030-IDC-NL-2SIDE")
      (libsource (lib "eagle-import") (part "TC2030-JLINK-NL-2SIDE"))
    )
    (comp (ref "JP1")
      (value "JUMPER-SMT_2_NC_TRACE_SILK")
      (footprint "eagle-import:SMT-JUMPER_2_NC_TRACE_SILK")
      (libsource (lib "eagle-import") (part "JUMPER-SMT_2_NC_TRACE_SILK"))
    )
    (comp (ref "R2")
      (value "5.1")
      (footprint "eagle-import:0402_RES")
      (fields (field (name "MPN") "RC0402JR-075R1L"))
      (libsource (lib "eagle-import") (part "RESISTOR0402_RES"))
    )
    (comp (ref "R3")
      (value "5.1")
      (footprint "eagle-import:0402_RES")
      (fields (field (name "MPN") "RC0402JR-075R1L"))
      (libsource (lib "eagle-import") (part "RESISTOR0402_RES"))
    )
    (comp (ref "R4")
      (value "15")
      (footprint "eagle-import:0402_RES")
      (fields (field (name "MPN") "RC0402JR-0715RL"))
      (libsource (lib "eagle-import") (part "RESISTOR0402_RES"))
    )
    (comp (ref "R5")
      (value "15")
      (footprint "eagle-import:0402_RES")
      (fields (field (name "MPN") "RC0402JR-0715RL"))
      (libsource (lib "eagle-import") (part "RESISTOR0402_RES"))
    )
    (comp (ref "RZ6")
      (value "0")
      (footprint "eagle-import:0402_RES")
      (fields (field (name "MPN") "RMCF0402ZT0R00"))
      (libsource (lib "eagle-import") (part "passives_20904581_RESISTOR0402_RES"))
    )
    (comp (ref "RZ7")
      (value "0")
      (footprint "eagle-import:0402_RES")
      (fields (field (name "MPN") "RMCF0402ZT0R00"))
      (libsource (lib "eagle-import") (part "passives_20904581_RESISTOR0402_RES"))
    )
    (comp (ref "RZ8")
      (value "0")
      (footprint "eagle-import:0402_RES")
      (fields (field (name "MPN") "RMCF0402ZT0R00"))
      (libsource (lib "eagle-import") (part "passives_20904581_RESISTOR0402_RES"))
    )
    (comp (ref "RZ10")
      (value "0")
      (footprint "eagle-import:0402_RES")
      (fields (field (name "MPN") "RMCF0402ZT0R00"))
      (libsource (lib "eagle-import") (part "passives_20904581_RESISTOR0402_RES"))
    )
    (comp (ref "RZ11")
      (value "0")
      (footprint "eagle-import:0402_RES")
      (fields (field (name "MPN") "RMCF0402ZT0R00"))
      (libsource (lib "eagle-import") (part "passives_20904581_RESISTOR0402_RES"))
    )
    (comp (ref "VR2")
      (value "TPS7A0218PDQNR")
      (footprint "eagle-import:4-XDFN-EP")
      (libsource (lib "eagle-import") (part "TPS7A0218PDQNR"))
    )
    (comp (ref "C7")
      (value "22pF")
      (footprint "eagle-import:0201_CAP")
      (fields (field (name "MPN") "GRM0335C1H220FA01D"))
      (libsource (lib "eagle-import") (part "passives_20904581_CAPACITOR0201_CAP"))
    )
    (comp (ref "C8")
      (value "22pF")
      (footprint "eagle-import:0201_CAP")
      (fields (field (name "MPN") "GRM0335C1H220FA01D"))
      (libsource (lib "eagle-import") (part "passives_20904581_CAPACITOR0201_CAP"))
    )
    (comp (ref "C9")
      (value "470pF")
      (footprint "eagle-import:0402_CAP")
      (description "CAP CER 470PF 50V C0G/NP0 0402")
      (fields (field (name "MANUFACTURER") "Murata") (field (name "MPN") "GRM1555C1H471JA01J"))
      (libsource (lib "eagle-import") (part "passives_20904581_CAPACITOR0402_CAP"))
    )
    (comp (ref "C10")
      (value "470pF")
      (footprint "eagle-import:0402_CAP")
      (description "CAP CER 470PF 50V C0G/NP0 0402")
      (fields (field (name "MANUFACTURER") "Murata") (field (name "MPN") "GRM1555C1H471JA01J"))
      (libsource (lib "eagle-import") (part "passives_20904581_CAPACITOR0402_CAP"))
    )
    (comp (ref "C15")
      (value "10nF")
      (footprint "eagle-import:0402_CAP")
      (fields (field (name "MPN") "GRM155R71H103KA88J"))
      (libsource (lib "eagle-import") (part "passives_20904581_CAPACITOR0402_CAP"))
    )
    (comp (ref "C16")
      (value "10nF")
      (footprint "eagle-import:0402_CAP")
      (fields (field (name "MPN") "GRM155R71H103KA88J"))
      (libsource (lib "eagle-import") (part "passives_20904581_CAPACITOR0402_CAP"))
    )
    (comp (ref "C17")
      (value "22nF")
      (footprint "eagle-import:0402_CAP")
      (fields (field (name "MPN") "GRM155R71E223JA61D"))
      (libsource (lib "eagle-import") (part "passives_20904581_CAPACITOR0402_CAP"))
    )
    (comp (ref "C18")
      (value "22nF")
      (footprint "eagle-import:0402_CAP")
      (fields (field (name "MPN") "GRM155R71E223JA61D"))
      (libsource (lib "eagle-import") (part "passives_20904581_CAPACITOR0402_CAP"))
    )
    (comp (ref "C19")
      (value "22nF")
      (footprint "eagle-import:0402_CAP")
      (fields (field (name "MPN") "GRM155R71E223JA61D"))
      (libsource (lib "eagle-import") (part "passives_20904581_CAPACITOR0402_CAP"))
    )
    (comp (ref "C20")
      (value "22nF")
      (footprint "eagle-import:0402_CAP")
      (fields (field (name "MPN") "CC0402ZRY5V8BB223"))
      (libsource (lib "eagle-import") (part "passives_20904581_CAPACITOR0402_CAP"))
    )
    (comp (ref "C21")
      (value "22nF")
      (footprint "eagle-import:0402_CAP")
      (fields (field (name "MPN") "CC0402ZRY5V8BB223"))
      (libsource (lib "eagle-import") (part "passives_20904581_CAPACITOR0402_CAP"))
    )
    (comp (ref "C27")
      (value "0.1uF")
      (footprint "eagle-import:0402_CAP")
      (fields (field (name "MPN") "GRM155R71C104KA88J "))
      (libsource (lib "eagle-import") (part "CAPACITOR0402_CAP"))
    )
    (comp (ref "C28")
      (value "0.1uF")
      (footprint "eagle-import:0402_CAP")
      (fields (field (name "MPN") "GRM155R71C104KA88J "))
      (libsource (lib "eagle-import") (part "CAPACITOR0402_CAP"))
    )
    (comp (ref "C29")
      (value "0.1uF")
      (footprint "eagle-import:0402_CAP")
      (fields (field (name "MPN") "GRM155R71C104KA88J "))
      (libsource (lib "eagle-import") (part "CAPACITOR0402_CAP"))
    )
    (comp (ref "C30")
      (value "0.1uF")
      (footprint "eagle-import:0402_CAP")
      (fields (field (name "MPN") "GRM155R71C104KA88J "))
      (libsource (lib "eagle-import") (part "CAPACITOR0402_CAP"))
    )
    (comp (ref "C38")
      (value "0.47uF")
      (footprint "eagle-import:0402_CAP")
      (fields (field (name "MPN") "GRT155R61E474ME01D"))
      (libsource (lib "eagle-import") (part "passives_20904581_CAPACITOR0402_CAP"))
    )
    (comp (ref "C39")
      (value "0.47uF")
      (footprint "eagle-import:0402_CAP")
      (fields (field (name "MPN") "GRT155R61E474ME01D"))
      (libsource (lib "eagle-import") (part "passives_20904581_CAPACITOR0402_CAP"))
    )
    (comp (ref "C40")
      (value "1uF")
      (footprint "eagle-import:0402_CAP")
      (fields (field (name "MPN") "GRM155R70J105KA12J"))
      (libsource (lib "eagle-import") (part "CAPACITOR0402_CAP"))
    )
    (comp (ref "C41")
      (value "1uF")
      (footprint "eagle-import:0402_CAP")
      (fields (field (name "MPN") "GRM155R70J105KA12J"))
      (libsource (lib "eagle-import") (part "CAPACITOR0402_CAP"))
    )
    (comp (ref "C42")
      (value "1uF")
      (footprint "eagle-import:0402_CAP")
      (fields (field (name "MPN") "GRM155R70J105KA12J"))
      (libsource (lib "eagle-import") (part "CAPACITOR0402_CAP"))
    )
    (comp (ref "C45")
      (value "4.7uF")
      (footprint "eagle-import:0603_CAP")
      (fields (field (name "MPN") "C1608X7S1A475K080AC"))
      (libsource (lib "eagle-import") (part "passives_20904581_CAPACITOR0603_CAP"))
    )
    (comp (ref "C46")
      (value "4.7uF")
      (footprint "eagle-import:0603_CAP")
      (fields (field (name "MPN") "C1608X7S1A475K080AC"))
      (libsource (lib "eagle-import") (part "passives_20904581_CAPACITOR0603_CAP"))
    )
    (comp (ref "C47")
      (value "4.7uF")
      (footprint "eagle-import:0603_CAP")
      (fields (field (name "MPN") "C1608X7S1A475K080AC"))
      (libsource (lib "eagle-import") (part "passives_20904581_CAPACITOR0603_CAP"))
    )
    (comp (ref "C48")
      (value "4.7uF")
      (footprint "eagle-import:0603_CAP")
      (fields (field (name "MPN") "C1608X7S1A475K080AC"))
      (libsource (lib "eagle-import") (part "passives_20904581_CAPACITOR0603_CAP"))
    )
    (comp (ref "C53")
      (value "10uF")
      (footprint "eagle-import:0603_CAP")
      (fields (field (name "MPN") "CM105X5R106M25AT"))
      (libsource (lib "eagle-import") (part "passives_20904581_CAPACITOR0603_CAP"))
    )
    (comp (ref "C56")
      (value "10uF")
      (footprint "eagle-import:0603_CAP")
      (fields (field (name "MPN") "CM105X5R106M25AT"))
      (libsource (lib "eagle-import") (part "passives_20904581_CAPACITOR0603_CAP"))
    )
    (comp (ref "C57")
      (value "10uF")
      (footprint "eagle-import:0603_CAP")
      (fields (field (name "MPN") "CM105X5R106M25AT"))
      (libsource (lib "eagle-import") (part "passives_20904581_CAPACITOR0603_CAP"))
    )
    (comp (ref "J4")
      (value "MOLEX-PICO-SPOX-3SIDE")
      (footprint "eagle-import:MOLEX-PICO-SPOX-3_SIDE")
      (libsource (lib "eagle-import") (part "MOLEX-PICO-SPOX-3SIDE"))
    )
    (comp (ref "JP2")
      (value "JUMPER-SMT_3_1-NC_TRACE_SILK")
      (footprint "eagle-import:SMT-JUMPER_3_1-NC_TRACE_SILK")
      (libsource (lib "eagle-import") (part "JUMPER-SMT_3_1-NC_TRACE_SILK"))
    )
    (comp (ref "JP9")
      (value "PINHD-1X2")
      (footprint "eagle-import:1X02")
      (libsource (lib "eagle-import") (part "PINHD-1X2"))
    )
    (comp (ref "JP10")
      (value "PINHD-1X1")
      (footprint "eagle-import:1X01")
      (libsource (lib "eagle-import") (part "PINHD-1X1"))
    )
    (comp (ref "JP11")
      (value "PINHD-1X1")
      (footprint "eagle-import:1X01")
      (libsource (lib "eagle-import") (part "PINHD-1X1"))
    )
    (comp (ref "L1")
      (value "10uH")
      (footprint "eagle-import:NRX3015")
      (fields (field (name "MANUFACTURER") "TAIYO YUDEN") (field (name "MPN") "NR3015T100M"))
      (libsource (lib "eagle-import") (part "INDUCTORNRX3015"))
    )
    (comp (ref "L2")
      (value "10uH")
      (footprint "eagle-import:NRX3015")
      (fields (field (name "MANUFACTURER") "TAIYO YUDEN") (field (name "MPN") "NR3015T100M"))
      (libsource (lib "eagle-import") (part "INDUCTORNRX3015"))
    )
    (comp (ref "L4")
      (value "WURTH_COIL_760308103204")
      (footprint "eagle-import:WURTH_COIL_760308103204")
      (fields (field (name "MANUFACTURER") "Würth Elektronik") (field (name "MPN") "760308103204"))
      (libsource (lib "eagle-import") (part "WURTH_COIL_760308103204"))
    )
    (comp (ref "Q1")
      (value "CSD75207W15")
      (footprint "eagle-import:DSBGA")
      (fields (field (name "MANUFACTURER") "TEXAS INSTRUMENTS"))
      (libsource (lib "eagle-import") (part "CSD75207W15"))
    )
    (comp (ref "R6")
      (value "97.6")
      (footprint "eagle-import:0402_RES")
      (fields (field (name "MPN") "RMCF0402FT97R6"))
      (libsource (lib "eagle-import") (part "passives_20904581_RESISTOR0402_RES"))
    )
    (comp (ref "R7")
      (value "97.6")
      (footprint "eagle-import:0402_RES")
      (fields (field (name "MPN") "RMCF0402FT97R6"))
      (libsource (lib "eagle-import") (part "passives_20904581_RESISTOR0402_RES"))
    )
    (comp (ref "R8")
      (value "162")
      (footprint "eagle-import:0402_RES")
      (fields (field (name "MPN") "RMCF0402FT162R"))
      (libsource (lib "eagle-import") (part "passives_20904581_RESISTOR0402_RES"))
    )
    (comp (ref "R9")
      (value "162")
      (footprint "eagle-import:0402_RES")
      (fields (field (name "MPN") "RMCF0402FT162R"))
      (libsource (lib "eagle-import") (part "passives_20904581_RESISTOR0402_RES"))
    )
    (comp (ref "R13")
      (value "1k")
      (footprint "eagle-import:0402_RES")
      (libsource (lib "eagle-import") (part "RESISTOR0402_RES"))
    )
    (comp (ref "R14")
      (value "1k")
      (footprint "eagle-import:0402_RES")
      (libsource (lib "eagle-import") (part "RESISTOR0402_RES"))
    )
    (comp (ref "R15")
      (value "2.2k")
      (footprint "eagle-import:0402_RES")
      (fields (field (name "MPN") "RMCF0402JT2K20"))
      (libsource (lib "eagle-import") (part "passives_20904581_RESISTOR0402_RES"))
    )
    (comp (ref "R18")
      (value "10k")
      (footprint "eagle-import:0402_RES")
      (fields (field (name "MPN") "RC0402JR-0710KL"))
      (libsource (lib "eagle-import") (part "RESISTOR0402_RES"))
    )
    (comp (ref "R23")
      (value "10k")
      (footprint "eagle-import:0402_RES")
      (fields (field (name "MPN") "RC0402JR-0710KL"))
      (libsource (lib "eagle-import") (part "RESISTOR0402_RES"))
    )
    (comp (ref "R26")
      (value "261k")
      (footprint "eagle-import:0201_RES")
      (fields (field (name "MPN") "ERJ-1GNF2613C"))
      (libsource (lib "eagle-import") (part "passives_20904581_RESISTOR0201_RES"))
    )
    (comp (ref "R27")
      (value "402k")
      (footprint "eagle-import:0201_RES")
      (fields (field (name "MPN") "ERJ-1GNF4023C"))
      (libsource (lib "eagle-import") (part "passives_20904581_RESISTOR0201_RES"))
    )
    (comp (ref "R28")
      (value "845k")
      (footprint "eagle-import:0201_RES")
      (fields (field (name "MPN") "ERJ-1GNF8453C"))
      (libsource (lib "eagle-import") (part "passives_20904581_RESISTOR0201_RES"))
    )
    (comp (ref "R29")
      (value "845k")
      (footprint "eagle-import:0201_RES")
      (fields (field (name "MPN") "ERJ-1GNF8453C"))
      (libsource (lib "eagle-import") (part "passives_20904581_RESISTOR0201_RES"))
    )
    (comp (ref "R30")
      (value "1.87M")
      (footprint "eagle-import:0402_RES")
      (fields (field (name "MPN") "RMCF0402FT1M87") (field (name "TOLERANCE") "1%"))
      (libsource (lib "eagle-import") (part "RESISTOR0402_RES"))
    )
    (comp (ref "R31")
      (value "5.1M")
      (footprint "eagle-import:0402_RES")
      (fields (field (name "MPN") "RMCF0402FT5M10") (field (name "TOLERANCE") "1%"))
      (libsource (lib "eagle-import") (part "RESISTOR0402_RES"))
    )
    (comp (ref "R33")
      (value "5.1M")
      (footprint "eagle-import:0402_RES")
      (fields (field (name "MPN") "RMCF0402FT5M10"))
      (libsource (lib "eagle-import") (part "RESISTOR0402_RES"))
    )
    (comp (ref "R34")
      (value "5.1M")
      (footprint "eagle-import:0402_RES")
      (fields (field (name "MPN") "RMCF0402FT5M10"))
      (libsource (lib "eagle-import") (part "RESISTOR0402_RES"))
    )
    (comp (ref "RT1")
      (value "10k@25C")
      (footprint "eagle-import:0402_RES")
      (fields (field (name "MPN") "NCU15XH103F60RC"))
      (libsource (lib "eagle-import") (part "THERMISTOR0402"))
    )
    (comp (ref "RX7")
      (value "DNP")
      (footprint "eagle-import:0402_RES")
      (libsource (lib "eagle-import") (part "passives_20904581_RESISTOR0402_RES"))
    )
    (comp (ref "S1")
      (value "450404015514")
      (footprint "eagle-import:450404015514")
      (libsource (lib "eagle-import") (part "450404015514"))
    )
    (comp (ref "U3")
      (value "BQ24040")
      (footprint "eagle-import:DSQ0010A")
      (fields (field (name "MPN") "BQ24040DSQR"))
      (libsource (lib "eagle-import") (part "BQ24040"))
    )
    (comp (ref "U4")
      (value "BQ51013B")
      (footprint "eagle-import:RHL0020A")
      (fields (field (name "MPN") "BQ51013BRHLR"))
      (libsource (lib "eagle-import") (part "BQ51013B"))
    )
    (comp (ref "VR1")
      (value "RT8020RT8020GQW")
      (footprint "eagle-import:SON45P300X300X80-13T160X250N")
      (fields (field (name "MANUFACTURER") "RichTek") (field (name "MPN") "RT8020GQW"))
      (libsource (lib "eagle-import") (part "RT8020RT8020GQW"))
    )
    (comp (ref "XJ1")
      (value "USB4110-GF-A")
      (footprint "eagle-import:GCT_USB4110-GF-A")
      (fields (field (name "MF") "GCT"))
      (libsource (lib "eagle-import") (part "USB4110-GF-A"))
    )
    (comp (ref "XR16")
      (value "5.1k")
      (footprint "eagle-import:0402_RES")
      (fields (field (name "MPN") "RMCF0402FT5K10"))
      (libsource (lib "eagle-import") (part "passives_20904581_RESISTOR0402_RES"))
    )
    (comp (ref "XR17")
      (value "5.1k")
      (footprint "eagle-import:0402_RES")
      (fields (field (name "MPN") "RMCF0402FT5K10"))
      (libsource (lib "eagle-import") (part "passives_20904581_RESISTOR0402_RES"))
    )
    (comp (ref "XR19")
      (value "10k")
      (footprint "eagle-import:0402_RES")
      (fields (field (name "MPN") "RC0402JR-0710KL"))
      (libsource (lib "eagle-import") (part "RESISTOR0402_RES"))
    )
    (comp (ref "FD1")
      (value "FIDUCIAL")
      (footprint "eagle-import:FIDUCIAL_1MM-CU_2MM-MASK")
      (libsource (lib "eagle-import") (part "FIDUCIAL"))
    )
    (comp (ref "FD2")
      (value "FIDUCIAL")
      (footprint "eagle-import:FIDUCIAL_1MM-CU_2MM-MASK")
      (libsource (lib "eagle-import") (part "FIDUCIAL"))
    )
    (comp (ref "FD4")
      (value "FIDUCIAL")
      (footprint "eagle-import:FIDUCIAL_1MM-CU_2MM-MASK")
      (libsource (lib "eagle-import") (part "FIDUCIAL"))
    )
    (comp (ref "FD6")
      (value "FIDUCIAL")
      (footprint "eagle-import:FIDUCIAL_1MM-CU_2MM-MASK")
      (libsource (lib "eagle-import") (part "FIDUCIAL"))
    )
    (comp (ref "C5")
      (value "4pF")
      (footprint "eagle-import:0201_CAP")
      (fields (field (name "MANUFACTURER") "Murata") (field (name "MPN") "GRM0335C1H4R0BA01D"))
      (libsource (lib "eagle-import") (part "passives_20904581_CAPACITOR0201_CAP"))
    )
    (comp (ref "C6")
      (value "4pF")
      (footprint "eagle-import:0201_CAP")
      (fields (field (name "MANUFACTURER") "Murata") (field (name "MPN") "GRM0335C1H4R0BA01D"))
      (libsource (lib "eagle-import") (part "passives_20904581_CAPACITOR0201_CAP"))
    )
    (comp (ref "C31")
      (value "0.1uF")
      (footprint "eagle-import:0402_CAP")
      (fields (field (name "MPN") "CL05A104KP5NNNC"))
      (libsource (lib "eagle-import") (part "passives_20904581_CAPACITOR0402_CAP"))
    )
    (comp (ref "C32")
      (value "0.1uF")
      (footprint "eagle-import:0402_CAP")
      (fields (field (name "MPN") "CL05A104KP5NNNC"))
      (libsource (lib "eagle-import") (part "passives_20904581_CAPACITOR0402_CAP"))
    )
    (comp (ref "C35")
      (value "0.1uF")
      (footprint "eagle-import:0402_CAP")
      (fields (field (name "MPN") "CL05A104KP5NNNC"))
      (libsource (lib "eagle-import") (part "passives_20904581_CAPACITOR0402_CAP"))
    )
    (comp (ref "C36")
      (value "0.1uF")
      (footprint "eagle-import:0402_CAP")
      (fields (field (name "MPN") "CL05A104KP5NNNC"))
      (libsource (lib "eagle-import") (part "CAPACITOR0402_CAP"))
    )
    (comp (ref "C44")
      (value "1uF")
      (footprint "eagle-import:0402_CAP")
      (fields (field (name "MPN") "GRM155R70J105KA12J"))
      (libsource (lib "eagle-import") (part "CAPACITOR0402_CAP"))
    )
    (comp (ref "D4")
      (value "DIODE0402")
      (footprint "eagle-import:0402_DIODE")
      (fields (field (name "MPN") "CDSQR400B-HF"))
      (libsource (lib "eagle-import") (part "DIODE0402"))
    )
    (comp (ref "LS1")
      (value "PUI_SMT-0440-T-2-R")
      (footprint "eagle-import:SMT-0440-T-2-R")
      (fields (field (name "MPN") "SMT-0440-T-2-R"))
      (libsource (lib "eagle-import") (part "PUI_SMT-0440-T-2-R"))
    )
    (comp (ref "Q2")
      (value "MOSFET-NCHANNELXFDN-3")
      (footprint "eagle-import:XFDFN-3")
      (libsource (lib "eagle-import") (part "MOSFET-NCHANNELXFDN-3"))
    )
    (comp (ref "R12")
      (value "10k")
      (footprint "eagle-import:0402_RES")
      (fields (field (name "MPN") "RC0402JR-0710KL"))
      (libsource (lib "eagle-import") (part "RESISTOR0402_RES"))
    )
    (comp (ref "R16")
      (value "10k")
      (footprint "eagle-import:0402_RES")
      (fields (field (name "MPN") "RC0402JR-0710KL"))
      (libsource (lib "eagle-import") (part "RESISTOR0402_RES"))
    )
    (comp (ref "R20")
      (value "10k")
      (footprint "eagle-import:0402_RES")
      (fields (field (name "MPN") "RC0402JR-0710KL"))
      (libsource (lib "eagle-import") (part "RESISTOR0402_RES"))
    )
    (comp (ref "R25")
      (value "100k")
      (footprint "eagle-import:0402_RES")
      (fields (field (name "MPN") "RT0402BRE07100KL"))
      (libsource (lib "eagle-import") (part "RESISTOR0402_RES"))
    )
    (comp (ref "RX2")
      (value "DNP")
      (footprint "eagle-import:0603-RES")
      (libsource (lib "eagle-import") (part "passives_20904581_RESISTOR0603_RES"))
    )
    (comp (ref "RX5")
      (value "DNP")
      (footprint "eagle-import:0603-RES")
      (libsource (lib "eagle-import") (part "passives_20904581_RESISTOR0603_RES"))
    )
    (comp (ref "RX6")
      (value "DNP")
      (footprint "eagle-import:0603-RES")
      (libsource (lib "eagle-import") (part "passives_20904581_RESISTOR0603_RES"))
    )
    (comp (ref "RX8")
      (value "DNP")
      (footprint "eagle-import:0603-RES")
      (libsource (lib "eagle-import") (part "passives_20904581_RESISTOR0603_RES"))
    )
    (comp (ref "RX9")
      (value "DNP")
      (footprint "eagle-import:0603-RES")
      (libsource (lib "eagle-import") (part "passives_20904581_RESISTOR0603_RES"))
    )
    (comp (ref "RZ12")
      (value "0")
      (footprint "eagle-import:0402_RES")
      (fields (field (name "MPN") "RMCF0402ZT0R00"))
      (libsource (lib "eagle-import") (part "passives_20904581_RESISTOR0402_RES"))
    )
    (comp (ref "U6")
      (value "BNO086")
      (footprint "eagle-import:LGA28R0P510X4_5P2X3P8X1")
      (fields (field (name "MANUFACTURER") "CEVA Technologies, Inc."))
      (libsource (lib "eagle-import") (part "BNO086"))
    )
    (comp (ref "U8")
      (value "AS5FXXX04SND")
      (footprint "eagle-import:AS5FXXXXXXXX-XXLXN")
      (fields (field (name "MANUFACTURER") "Alliance Memory") (field (name "MPN") "AS5F18G04SND-10LIN"))
      (libsource (lib "eagle-import") (part "AS5FXXX04SND"))
    )
    (comp (ref "X2")
      (value "TXC-9HT12")
      (footprint "eagle-import:TXC-9HT12")
      (fields
        (field (name "C-LOAD") "7pF")
        (field (name "FREQUENCY") "32.768 kHz")
        (field (name "MANUFACTURER") "TXC Corp")
        (field (name "MPN") "9HT12-32.768KDZY-T")
      )
      (libsource (lib "eagle-import") (part "TXC-9HT12"))
    )
  )
  (nets
    (net (code "1") (name "+1V8") (class "Default")
      (node (ref "C26") (pin "1") (pinfunction "1_1") (pintype "bidirectional"))
      (node (ref "C31") (pin "1") (pinfunction "1_1") (pintype "bidirectional"))
      (node (ref "C35") (pin "1") (pinfunction "1_1") (pintype "bidirectional"))
      (node (ref "C46") (pin "1") (pinfunction "1_1") (pintype "bidirectional"))
      (node (ref "C50") (pin "2") (pinfunction "2_2") (pintype "bidirectional"))
      (node (ref "C62") (pin "P$1") (pinfunction "1_P$1") (pintype "bidirectional"))
      (node (ref "C63") (pin "P$1") (pinfunction "1_P$1") (pintype "bidirectional"))
      (node (ref "C64") (pin "P$1") (pinfunction "1_P$1") (pintype "bidirectional"))
      (node (ref "C65") (pin "P$1") (pinfunction "1_P$1") (pintype "bidirectional"))
      (node (ref "C66") (pin "P$1") (pinfunction "1_P$1") (pintype "bidirectional"))
      (node (ref "C67") (pin "P$1") (pinfunction "1_P$1") (pintype "bidirectional"))
      (node (ref "C75") (pin "P$2") (pinfunction "2_P$2") (pintype "bidirectional"))
      (node (ref "C8") (pin "P$2") (pinfunction "2_P$2") (pintype "bidirectional"))
      (node (ref "J1") (pin "1") (pinfunction "VTREF_1") (pintype "bidirectional"))
      (node (ref "J1") (pin "B1") (pinfunction "VTREF_B1") (pintype "bidirectional"))
      (node (ref "JP1") (pin "2") (pinfunction "2_2") (pintype "passive"))
      (node (ref "JP11") (pin "1") (pinfunction "1_1") (pintype "passive"))
      (node (ref "JP12") (pin "1") (pinfunction "1_1") (pintype "passive"))
      (node (ref "L2") (pin "P$1") (pinfunction "1_P$1") (pintype "bidirectional"))
      (node (ref "R12") (pin "2") (pinfunction "2_2") (pintype "passive"))
      (node (ref "R16") (pin "2") (pinfunction "2_2") (pintype "passive"))
      (node (ref "R20") (pin "2") (pinfunction "2_2") (pintype "passive"))
      (node (ref "R29") (pin "1") (pinfunction "1_1") (pintype "passive"))
      (node (ref "RX2") (pin "2") (pinfunction "2_2") (pintype "passive"))
      (node (ref "RX5") (pin "1") (pinfunction "1_1") (pintype "passive"))
      (node (ref "RX6") (pin "1") (pinfunction "1_1") (pintype "passive"))
      (node (ref "RX8") (pin "2") (pinfunction "2_2") (pintype "passive"))
      (node (ref "RZ12") (pin "2") (pinfunction "2_2") (pintype "passive"))
      (node (ref "S3") (pin "4") (pinfunction "IN_4") (pintype "bidirectional"))
      (node (ref "TP9") (pin "P$1") (pinfunction "TESTPOINT_P$1") (pintype "bidirectional"))
      (node (ref "U1") (pin "B1") (pinfunction "VDDP-IO_PAD_SUP_B1") (pintype "bidirectional"))
      (node (ref "U1") (pin "C4") (pinfunction "VDDA-ANALOG_SUP_C4") (pintype "bidirectional"))
      (node (ref "U1") (pin "E11") (pinfunction "VDDAUDD_E11") (pintype "bidirectional"))
      (node (ref "U1") (pin "G1") (pinfunction "VDDB-BLE_SUPPLY_G1") (pintype "bidirectional"))
      (node (ref "U1") (pin "M10") (pinfunction "VDDH-HV_SUP_M10") (pintype "bidirectional"))
      (node (ref "U1") (pin "M9") (pinfunction "VDDH2-HV_SUP_M9") (pintype "bidirectional"))
      (node (ref "U2") (pin "B13") (pinfunction "VDD1_B13") (pintype "bidirectional"))
      (node (ref "U6") (pin "28") (pinfunction "VDDIO_28") (pintype "input"))
      (node (ref "U8") (pin "8") (pinfunction "VCC_8") (pintype "bidirectional"))
    )
    (net (code "2") (name "+2V5") (class "Default")
      (node (ref "C32") (pin "1") (pinfunction "1_1") (pintype "bidirectional"))
      (node (ref "C34") (pin "1") (pinfunction "1_1") (pintype "bidirectional"))
      (node (ref "C44") (pin "1") (pinfunction "1_1") (pintype "bidirectional"))
      (node (ref "C47") (pin "2") (pinfunction "2_2") (pintype "bidirectional"))
      (node (ref "C49") (pin "1") (pinfunction "1_1") (pintype "bidirectional"))
      (node (ref "C7") (pin "P$1") (pinfunction "1_P$1") (pintype "bidirectional"))
      (node (ref "C77") (pin "P$1") (pinfunction "1_P$1") (pintype "bidirectional"))
      (node (ref "C90") (pin "P$1") (pinfunction "1_P$1") (pintype "bidirectional"))
      (node (ref "D4") (pin "CATHODE") (pinfunction "CATHODE_CATHODE") (pintype "bidirectional"))
      (node (ref "JP10") (pin "1") (pinfunction "1_1") (pintype "passive"))
      (node (ref "L1") (pin "P$2") (pinfunction "2_P$2") (pintype "bidirectional"))
      (node (ref "LS1") (pin "+") (pinfunction "P_+") (pintype "passive"))
      (node (ref "R28") (pin "2") (pinfunction "2_2") (pintype "passive"))
      (node (ref "RX1") (pin "1") (pinfunction "1_1") (pintype "passive"))
      (node (ref "RZ10") (pin "1") (pinfunction "1_1") (pintype "passive"))
      (node (ref "S2") (pin "6") (pinfunction "VDD_6") (pintype "power_in"))
      (node (ref "S3") (pin "1") (pinfunction "IN_1") (pintype "bidirectional"))
      (node (ref "U6") (pin "3") (pinfunction "VDD_3") (pintype "input"))
      (node (ref "VR2") (pin "4") (pinfunction "IN_4") (pintype "bidirectional"))
      (node (ref "VR3") (pin "4") (pinfunction "IN_4") (pintype "bidirectional"))
    )
    (net (code "3") (name "AGND") (class "Default")
      (node (ref "C1") (pin "2") (pinfunction "2_2") (pintype "passive"))
      (node (ref "C93") (pin "P$2") (pinfunction "2_P$2") (pintype "bidirectional"))
      (node (ref "CX5") (pin "2") (pinfunction "2_2") (pintype "passive"))
      (node (ref "U1") (pin "M1") (pinfunction "RFIOM_M1") (pintype "bidirectional"))
      (node (ref "U1") (pin "M3") (pinfunction "RFSUB-RF_SUBSTRATE_GND_M3") (pintype "bidirectional"))
    )
    (net (code "4") (name "ANT1") (class "Default")
      (node (ref "A1") (pin "FEED") (pinfunction "ANTENNA_FEED") (pintype "bidirectional"))
      (node (ref "U7") (pin "2") (pinfunction "LNA_IN_2") (pintype "bidirectional"))
    )
    (net (code "5") (name "AP4_GP06{slash}TT_FLASH_~{HOLD_IO3}") (class "Default")
      (node (ref "U1") (pin "J5") (pinfunction "GPIO6_J5") (pintype "bidirectional"))
      (node (ref "U8") (pin "7") (pinfunction "~{HOLD}/SIO3_7") (pintype "bidirectional"))
    )
    (net (code "6") (name "AP4_GP08{slash}TT_9DOF_H_SCL{slash}SCK{slash}RX") (class "Default")
      (node (ref "RX6") (pin "2") (pinfunction "2_2") (pintype "passive"))
      (node (ref "U1") (pin "H2") (pinfunction "GPIO31_H2") (pintype "bidirectional"))
      (node (ref "U6") (pin "19") (pinfunction "H_SCL/SCK/RX_19") (pintype "bidirectional"))
    )
    (net (code "7") (name "AP4_GP09{slash}TT_9DOF_H_SDA{slash}H_MISO{slash}TX") (class "Default")
      (node (ref "RX5") (pin "2") (pinfunction "2_2") (pintype "passive"))
      (node (ref "U1") (pin "G2") (pinfunction "GPIO32_G2") (pintype "bidirectional"))
      (node (ref "U6") (pin "20") (pinfunction "H_SDA/H_MISO/TX_20") (pintype "bidirectional"))
    )
    (net (code "8") (name "AP4_GP10{slash}TT_9DOF_SA0{slash}H_MOSI") (class "Default")
      (node (ref "U1") (pin "G3") (pinfunction "GPIO33_G3") (pintype "bidirectional"))
      (node (ref "U6") (pin "17") (pinfunction "SA0/H_MOSI_17") (pintype "input"))
    )
    (net (code "9") (name "AP4_GP13{slash}TT_9DOF_~{BOOT}") (class "Default")
      (node (ref "R20") (pin "1") (pinfunction "1_1") (pintype "passive"))
      (node (ref "U1") (pin "D5") (pinfunction "GPIO13_D5") (pintype "bidirectional"))
      (node (ref "U6") (pin "4") (pinfunction "~{BOOT}_4") (pintype "input"))
    )
    (net (code "10") (name "AP4_GP14{slash}TT_~{DW_SPI_CS}") (class "Default")
      (node (ref "U1") (pin "D6") (pinfunction "GPIO14_D6") (pintype "bidirectional"))
      (node (ref "U2") (pin "B5") (pinfunction "~{SPICS}_B5") (pintype "bidirectional"))
    )
    (net (code "11") (name "AP4_GP17{slash}TT_9DOF_H_~{INT}") (class "Default")
      (node (ref "U1") (pin "D4") (pinfunction "GPIO17_D4") (pintype "bidirectional"))
      (node (ref "U6") (pin "14") (pinfunction "H_INTN_14") (pintype "output"))
    )
    (net (code "12") (name "AP4_GP18{slash}TT_BATIN") (class "Default")
      (node (ref "C27") (pin "1") (pinfunction "1_1") (pintype "bidirectional"))
      (node (ref "R30") (pin "2") (pinfunction "2_2") (pintype "passive"))
      (node (ref "R31") (pin "1") (pinfunction "1_1") (pintype "passive"))
      (node (ref "U1") (pin "D3") (pinfunction "GPIO18_D3") (pintype "bidirectional"))
    )
    (net (code "13") (name "AP4_GP24{slash}TT_RFSW_V1") (class "Default")
      (node (ref "CX2") (pin "1") (pinfunction "1_1") (pintype "bidirectional"))
      (node (ref "S2") (pin "4") (pinfunction "V1_4") (pintype "input"))
      (node (ref "U1") (pin "E2") (pinfunction "GPIO24_E2") (pintype "bidirectional"))
    )
    (net (code "14") (name "AP4_GP25{slash}TT_RFSW_V2") (class "Default")
      (node (ref "CX1") (pin "1") (pinfunction "1_1") (pintype "bidirectional"))
      (node (ref "S2") (pin "5") (pinfunction "V2_5") (pintype "input"))
      (node (ref "U1") (pin "K5") (pinfunction "GPIO25_K5") (pintype "bidirectional"))
    )
    (net (code "15") (name "AP4_GP26{slash}TT_DW_WAKEUP") (class "Default")
      (node (ref "U1") (pin "L5") (pinfunction "GPIO26_L5") (pintype "bidirectional"))
      (node (ref "U2") (pin "B9") (pinfunction "WAKEUP_B9") (pintype "bidirectional"))
    )
    (net (code "16") (name "AP4_GP27{slash}TT_DW_IRQ") (class "Default")
      (node (ref "R24") (pin "2") (pinfunction "2_2") (pintype "passive"))
      (node (ref "U1") (pin "M5") (pinfunction "GPIO27_M5") (pintype "bidirectional"))
      (node (ref "U2") (pin "B1") (pinfunction "IRQ/GPIO8_B1") (pintype "bidirectional"))
    )
    (net (code "17") (name "AP4_GP30{slash}TT_FLASH_~{WP}") (class "Default")
      (node (ref "U1") (pin "G4") (pinfunction "GPIO30_G4") (pintype "bidirectional"))
      (node (ref "U8") (pin "3") (pinfunction "~{WP}/SIO2_3") (pintype "bidirectional"))
    )
    (net (code "18") (name "AP4_GP31{slash}TT_DW_SPI_CLK") (class "Default")
      (node (ref "U1") (pin "E8") (pinfunction "GPIO8_E8") (pintype "bidirectional"))
      (node (ref "U2") (pin "A8") (pinfunction "SPICLK_A8") (pintype "bidirectional"))
    )
    (net (code "19") (name "AP4_GP32{slash}TT_DW_SPI_IO0") (class "Default")
      (node (ref "U1") (pin "E7") (pinfunction "GPIO9_E7") (pintype "bidirectional"))
      (node (ref "U2") (pin "B7") (pinfunction "SPICDI(MOSI)_B7") (pintype "bidirectional"))
    )
    (net (code "20") (name "AP4_GP33{slash}TT_DW_SPI_IO1") (class "Default")
      (node (ref "U1") (pin "E6") (pinfunction "GPIO10_E6") (pintype "bidirectional"))
      (node (ref "U2") (pin "A6") (pinfunction "SPICDO(MISO)_A6") (pintype "bidirectional"))
    )
    (net (code "21") (name "AP4_GP47{slash}TT_FLASH_SCK") (class "Default")
      (node (ref "U1") (pin "F1") (pinfunction "GPIO47_F1") (pintype "bidirectional"))
      (node (ref "U8") (pin "6") (pinfunction "SCLK_6") (pintype "input"))
    )
    (net (code "22") (name "AP4_GP48{slash}TT_FLASH_PDI_IO0") (class "Default")
      (node (ref "U1") (pin "E1") (pinfunction "GPIO48_E1") (pintype "bidirectional"))
      (node (ref "U8") (pin "5") (pinfunction "SI/SIO0_5") (pintype "bidirectional"))
    )
    (net (code "23") (name "AP4_GP49{slash}TT_FLASH_PDO_IO1") (class "Default")
      (node (ref "U1") (pin "D1") (pinfunction "GPIO49_D1") (pintype "bidirectional"))
      (node (ref "U8") (pin "2") (pinfunction "SO/SIO1_2") (pintype "bidirectional"))
    )
    (net (code "24") (name "AP4_GP50{slash}TT_~{DW_RESET}") (class "Default")
      (node (ref "U1") (pin "A9") (pinfunction "GPIO50_A9") (pintype "bidirectional"))
      (node (ref "U2") (pin "A10") (pinfunction "~{RST}_A10") (pintype "bidirectional"))
    )
    (net (code "25") (name "AP4_GP51{slash}LED1_GREEN") (class "Default")
      (node (ref "R2") (pin "2") (pinfunction "2_2") (pintype "passive"))
      (node (ref "U1") (pin "B9") (pinfunction "GPIO51_B9") (pintype "bidirectional"))
    )
    (net (code "26") (name "AP4_GP53{slash}LED1_RED") (class "Default")
      (node (ref "R5") (pin "2") (pinfunction "2_2") (pintype "passive"))
      (node (ref "U1") (pin "C9") (pinfunction "GPIO53_C9") (pintype "bidirectional"))
    )
    (net (code "27") (name "AP4_GP55{slash}TT_BUZZER_GATE") (class "Default")
      (node (ref "Q2") (pin "G") (pinfunction "G_G") (pintype "passive"))
      (node (ref "R25") (pin "1") (pinfunction "1_1") (pintype "passive"))
      (node (ref "U1") (pin "D9") (pinfunction "GPIO55_D9") (pintype "bidirectional"))
    )
    (net (code "28") (name "AP4_GP58{slash}TT_~{CHG}") (class "Default")
      (node (ref "U1") (pin "J7") (pinfunction "GPIO58_J7") (pintype "bidirectional"))
      (node (ref "U3") (pin "8") (pinfunction "~{CHG}_8") (pintype "bidirectional"))
      (node (ref "U4") (pin "7") (pinfunction "~{CHG}_7") (pintype "bidirectional"))
    )
    (net (code "29") (name "AP4_GP60{slash}TT_~{PG}") (class "Default")
      (node (ref "U1") (pin "K8") (pinfunction "GPIO60_K8") (pintype "bidirectional"))
      (node (ref "U3") (pin "5") (pinfunction "~{PG}_5") (pintype "bidirectional"))
    )
    (net (code "30") (name "AP4_GP63{slash}TT_9DOF_PS0{slash}WAKE") (class "Default")
      (node (ref "U1") (pin "M6") (pinfunction "GPIO63_M6") (pintype "bidirectional"))
      (node (ref "U6") (pin "6") (pinfunction "PS0/WAKE_6") (pintype "input"))
    )
    (net (code "31") (name "AP4_GP65{slash}TT_9DOF_~{RESET}") (class "Default")
      (node (ref "RX8") (pin "1") (pinfunction "1_1") (pintype "passive"))
      (node (ref "U1") (pin "A7") (pinfunction "GPIO65_A7") (pintype "bidirectional"))
      (node (ref "U6") (pin "11") (pinfunction "~{RESET}_11") (pintype "input"))
    )
    (net (code "32") (name "AP4_GP66{slash}TT_QI_TS_CTRL") (class "Default")
      (node (ref "C30") (pin "1") (pinfunction "1_1") (pintype "bidirectional"))
      (node (ref "RT1") (pin "2") (pinfunction "2_2") (pintype "passive"))
      (node (ref "U1") (pin "A8") (pinfunction "GPIO66_A8") (pintype "bidirectional"))
      (node (ref "U4") (pin "13") (pinfunction "TS/CTRL_13") (pintype "bidirectional"))
    )
    (net (code "33") (name "AP4_GP69{slash}TT_FLASH_~{CS}") (class "Default")
      (node (ref "RX2") (pin "1") (pinfunction "1_1") (pintype "passive"))
      (node (ref "U1") (pin "B8") (pinfunction "GPIO69_B8") (pintype "bidirectional"))
      (node (ref "U8") (pin "1") (pinfunction "~{CS}_1") (pintype "input"))
    )
    (net (code "34") (name "AP4_GP72{slash}TT_9DOF_H_~{CS}") (class "Default")
      (node (ref "U1") (pin "C8") (pinfunction "GPIO72_C8") (pintype "bidirectional"))
      (node (ref "U6") (pin "18") (pinfunction "H_~{CS}_18") (pintype "input"))
    )
    (net (code "35") (name "AP4_GP79{slash}LED2_RED") (class "Default")
      (node (ref "R4") (pin "2") (pinfunction "2_2") (pintype "passive"))
      (node (ref "U1") (pin "M11") (pinfunction "GPIO79_M11") (pintype "bidirectional"))
    )
    (net (code "36") (name "AP4_GP80{slash}SWTRACE0") (class "Default")
      (node (ref "J2") (pin "2") (pinfunction "SWDIO_2") (pintype "bidirectional"))
      (node (ref "J2") (pin "B2") (pinfunction "SWDIO_B2") (pintype "bidirectional"))
      (node (ref "U1") (pin "K10") (pinfunction "GPIO80_K10") (pintype "bidirectional"))
    )
    (net (code "37") (name "AP4_GP81{slash}SWTRACE1") (class "Default")
      (node (ref "J2") (pin "4") (pinfunction "SWDCLK_4") (pintype "bidirectional"))
      (node (ref "J2") (pin "B4") (pinfunction "SWDCLK_B4") (pintype "bidirectional"))
      (node (ref "U1") (pin "L10") (pinfunction "GPIO81_L10") (pintype "bidirectional"))
    )
    (net (code "38") (name "AP4_GP82{slash}SWTRACE2") (class "Default")
      (node (ref "J2") (pin "6") (pinfunction "SWO_6") (pintype "bidirectional"))
      (node (ref "J2") (pin "B6") (pinfunction "SWO_B6") (pintype "bidirectional"))
      (node (ref "U1") (pin "L9") (pinfunction "GPIO82_L9") (pintype "bidirectional"))
    )
    (net (code "39") (name "AP4_GP83{slash}SWTRACE3") (class "Default")
      (node (ref "J2") (pin "3") (pinfunction "~{RESET}_3") (pintype "bidirectional"))
      (node (ref "J2") (pin "B3") (pinfunction "~{RESET}_B3") (pintype "bidirectional"))
      (node (ref "U1") (pin "K9") (pinfunction "GPIO83_K9") (pintype "bidirectional"))
    )
    (net (code "40") (name "AP4_GP88{slash}LED2_YLW") (class "Default")
      (node (ref "R3") (pin "2") (pinfunction "2_2") (pintype "passive"))
      (node (ref "U1") (pin "F9") (pinfunction "GPIO88_F9") (pintype "bidirectional"))
    )
    (net (code "41") (name "AP4_SWDCLK") (class "Default")
      (node (ref "J1") (pin "4") (pinfunction "SWDCLK_4") (pintype "bidirectional"))
      (node (ref "J1") (pin "B4") (pinfunction "SWDCLK_B4") (pintype "bidirectional"))
      (node (ref "U1") (pin "K3") (pinfunction "GPIO20_K3") (pintype "bidirectional"))
    )
    (net (code "42") (name "AP4_SWDIO") (class "Default")
      (node (ref "J1") (pin "2") (pinfunction "SWDIO_2") (pintype "bidirectional"))
      (node (ref "J1") (pin "B2") (pinfunction "SWDIO_B2") (pintype "bidirectional"))
      (node (ref "U1") (pin "J3") (pinfunction "GPIO21_J3") (pintype "bidirectional"))
    )
    (net (code "43") (name "AP4_SWO") (class "Default")
      (node (ref "J1") (pin "6") (pinfunction "SWO_6") (pintype "bidirectional"))
      (node (ref "J1") (pin "B6") (pinfunction "SWO_B6") (pintype "bidirectional"))
      (node (ref "U1") (pin "L4") (pinfunction "GPIO3_L4") (pintype "bidirectional"))
    )
    (net (code "44") (name "AP4_SWTRACECLK") (class "Default")
      (node (ref "J2") (pin "1") (pinfunction "VTREF_1") (pintype "bidirectional"))
      (node (ref "J2") (pin "B1") (pinfunction "VTREF_B1") (pintype "bidirectional"))
      (node (ref "U1") (pin "F12") (pinfunction "GPIO38_F12") (pintype "bidirectional"))
    )
    (net (code "45") (name "AP4_USB0_N") (class "Default")
      (node (ref "U1") (pin "M8") (pinfunction "USB0PN_M8") (pintype "bidirectional"))
    )
    (net (code "46") (name "AP4_USB0_P") (class "Default")
      (node (ref "U1") (pin "M7") (pinfunction "USB0PP_M7") (pintype "bidirectional"))
    )
    (net (code "47") (name "AP4_VDDBH") (class "Default")
      (node (ref "C69") (pin "1") (pinfunction "1_1") (pintype "bidirectional"))
      (node (ref "L6") (pin "2") (pinfunction "2_2") (pintype "bidirectional"))
      (node (ref "RZ9") (pin "1") (pinfunction "1_1") (pintype "passive"))
      (node (ref "TP8") (pin "P$1") (pinfunction "TESTPOINT_P$1") (pintype "bidirectional"))
      (node (ref "U1") (pin "G12") (pinfunction "VDDBH--BLE_BUCK_VOUT_G12") (pintype "bidirectional"))
    )
    (net (code "48") (name "AP4_VDDBH_RF") (class "Default")
      (node (ref "C93") (pin "P$1") (pinfunction "1_P$1") (pintype "bidirectional"))
      (node (ref "RZ9") (pin "2") (pinfunction "2_2") (pintype "passive"))
      (node (ref "U1") (pin "J1") (pinfunction "VDDBH_RF--BLE_BUCK_RF_VOUT_J1") (pintype "bidirectional"))
    )
    (net (code "49") (name "AP4_VDDF") (class "Default")
      (node (ref "C61") (pin "P$1") (pinfunction "1_P$1") (pintype "bidirectional"))
      (node (ref "C75") (pin "P$1") (pinfunction "1_P$1") (pintype "bidirectional"))
      (node (ref "TP10") (pin "P$1") (pinfunction "TESTPOINT_P$1") (pintype "bidirectional"))
      (node (ref "U1") (pin "C2") (pinfunction "VDDF-MEM_C2") (pintype "bidirectional"))
    )
    (net (code "50") (name "AP4_VDDMIPI_1P8") (class "Default")
      (node (ref "C70") (pin "P$1") (pinfunction "1_P$1") (pintype "bidirectional"))
      (node (ref "RZ8") (pin "1") (pinfunction "1_1") (pintype "passive"))
      (node (ref "U1") (pin "H10") (pinfunction "VDD18-MIPI_H10") (pintype "bidirectional"))
    )
    (net (code "51") (name "AP4_VDDUSB_0P9") (class "Default")
      (node (ref "C73") (pin "P$1") (pinfunction "1_P$1") (pintype "bidirectional"))
      (node (ref "RZ6") (pin "1") (pinfunction "1_1") (pintype "passive"))
      (node (ref "U1") (pin "L7") (pinfunction "VDDUSB0P9_L7") (pintype "bidirectional"))
    )
    (net (code "52") (name "AP4_VDDUSB_3P3") (class "Default")
      (node (ref "C74") (pin "P$1") (pinfunction "1_P$1") (pintype "bidirectional"))
      (node (ref "RZ7") (pin "1") (pinfunction "1_1") (pintype "passive"))
      (node (ref "U1") (pin "K7") (pinfunction "VDDUSB33_K7") (pintype "bidirectional"))
    )
    (net (code "53") (name "AP4_~{RESET}") (class "Default")
      (node (ref "C76") (pin "1") (pinfunction "1_1") (pintype "passive"))
      (node (ref "D3") (pin "1") (pinfunction "C_1") (pintype "passive"))
      (node (ref "J1") (pin "3") (pinfunction "~{RESET}_3") (pintype "bidirectional"))
      (node (ref "J1") (pin "B3") (pinfunction "~{RESET}_B3") (pintype "bidirectional"))
      (node (ref "U1") (pin "A6") (pinfunction "~{RST}_A6") (pintype "input"))
    )
    (net (code "54") (name "BATT_THERM") (class "Default")
      (node (ref "J4") (pin "2") (pinfunction "2_2") (pintype "bidirectional"))
      (node (ref "J4") (pin "2SUPP") (pinfunction "2_2SUPP") (pintype "bidirectional"))
      (node (ref "JP2") (pin "3") (pinfunction "3_3") (pintype "passive"))
    )
    (net (code "55") (name "BATT_TS") (class "Default")
      (node (ref "JP2") (pin "2") (pinfunction "2_2") (pintype "passive"))
      (node (ref "U3") (pin "9") (pinfunction "TS_9") (pintype "bidirectional"))
    )
    (net (code "56") (name "BNO_ENV_SCL") (class "Default")
      (node (ref "R12") (pin "1") (pinfunction "1_1") (pintype "passive"))
      (node (ref "U6") (pin "15") (pinfunction "ENV_SCL_15") (pintype "bidirectional"))
    )
    (net (code "57") (name "BNO_ENV_SDA") (class "Default")
      (node (ref "R16") (pin "1") (pinfunction "1_1") (pintype "passive"))
      (node (ref "U6") (pin "16") (pinfunction "ENV_SDA_16") (pintype "bidirectional"))
    )
    (net (code "58") (name "D+") (class "Default")
      (node (ref "XJ1") (pin "A6") (pinfunction "DP1_A6") (pintype "bidirectional"))
      (node (ref "XJ1") (pin "B6") (pinfunction "DP2_B6") (pintype "bidirectional"))
    )
    (net (code "59") (name "D-") (class "Default")
      (node (ref "XJ1") (pin "A7") (pinfunction "DN1_A7") (pintype "bidirectional"))
      (node (ref "XJ1") (pin "B7") (pinfunction "DN2_B7") (pintype "bidirectional"))
    )
    (net (code "60") (name "DW_EXTON") (class "Default")
      (node (ref "JP12") (pin "2") (pinfunction "2_2") (pintype "passive"))
      (node (ref "RX1") (pin "2") (pinfunction "2_2") (pintype "passive"))
      (node (ref "S3") (pin "2") (pinfunction "CTL_2") (pintype "bidirectional"))
      (node (ref "S3") (pin "3") (pinfunction "CTL_3") (pintype "bidirectional"))
      (node (ref "VR3") (pin "3") (pinfunction "EN_3") (pintype "input"))
    )
    (net (code "61") (name "DW_EXTON_RAW") (class "Default")
      (node (ref "JP12") (pin "3") (pinfunction "3_3") (pintype "passive"))
      (node (ref "U2") (pin "A12") (pinfunction "EXTON_A12") (pintype "bidirectional"))
    )
    (net (code "62") (name "DW_GPIO6{slash}EXTRXE") (class "Default")
      (node (ref "JP3") (pin "3") (pinfunction "3_3") (pintype "passive"))
      (node (ref "TP6") (pin "P$1") (pinfunction "TESTPOINT_P$1") (pintype "bidirectional"))
      (node (ref "U2") (pin "C4") (pinfunction "GPIO6/EXTRXE/SPIPHA_C4") (pintype "bidirectional"))
    )
    (net (code "63") (name "DW_SYNC") (class "Default")
      (node (ref "TP7") (pin "P$1") (pinfunction "TESTPOINT_P$1") (pintype "bidirectional"))
      (node (ref "U2") (pin "G2") (pinfunction "GPIO7/SYNC_G2") (pintype "bidirectional"))
    )
    (net (code "64") (name "DW_VDD2_SUP") (class "Default")
      (node (ref "C13") (pin "P$1") (pinfunction "P$1_P$1") (pintype "bidirectional"))
      (node (ref "C24") (pin "P$1") (pinfunction "P$1_P$1") (pintype "bidirectional"))
      (node (ref "C55") (pin "P$1") (pinfunction "P$1_P$1") (pintype "bidirectional"))
      (node (ref "FB1") (pin "P$1") (pinfunction "P$1_P$1") (pintype "bidirectional"))
      (node (ref "RZ1") (pin "2") (pinfunction "2_2") (pintype "passive"))
      (node (ref "U2") (pin "B15") (pinfunction "VDD2B_B15") (pintype "bidirectional"))
    )
    (net (code "65") (name "DW_VDD3_SUP") (class "Default")
      (node (ref "C14") (pin "P$2") (pinfunction "P$2_P$2") (pintype "bidirectional"))
      (node (ref "C22") (pin "P$2") (pinfunction "P$2_P$2") (pintype "bidirectional"))
      (node (ref "C54") (pin "P$2") (pinfunction "P$2_P$2") (pintype "bidirectional"))
      (node (ref "RZ2") (pin "2") (pinfunction "2_2") (pintype "passive"))
      (node (ref "U2") (pin "D15") (pinfunction "VDD3_D15") (pintype "bidirectional"))
    )
    (net (code "66") (name "GND") (class "Default")
      (node (ref "C11") (pin "P$2") (pinfunction "P$2_P$2") (pintype "bidirectional"))
      (node (ref "C12") (pin "P$2") (pinfunction "P$2_P$2") (pintype "bidirectional"))
      (node (ref "C13") (pin "P$2") (pinfunction "P$2_P$2") (pintype "bidirectional"))
      (node (ref "C14") (pin "P$1") (pinfunction "P$1_P$1") (pintype "bidirectional"))
      (node (ref "C22") (pin "P$1") (pinfunction "P$1_P$1") (pintype "bidirectional"))
      (node (ref "C23") (pin "2") (pinfunction "2_2") (pintype "bidirectional"))
      (node (ref "C24") (pin "P$2") (pinfunction "P$2_P$2") (pintype "bidirectional"))
      (node (ref "C25") (pin "2") (pinfunction "2_2") (pintype "bidirectional"))
      (node (ref "C26") (pin "2") (pinfunction "2_2") (pintype "bidirectional"))
      (node (ref "C27") (pin "2") (pinfunction "2_2") (pintype "bidirectional"))
      (node (ref "C28") (pin "2") (pinfunction "2_2") (pintype "bidirectional"))
      (node (ref "C29") (pin "2") (pinfunction "2_2") (pintype "bidirectional"))
      (node (ref "C3") (pin "P$2") (pinfunction "P$2_P$2") (pintype "bidirectional"))
      (node (ref "C30") (pin "2") (pinfunction "2_2") (pintype "bidirectional"))
      (node (ref "C31") (pin "2") (pinfunction "2_2") (pintype "bidirectional"))
      (node (ref "C32") (pin "2") (pinfunction "2_2") (pintype "bidirectional"))
      (node (ref "C33") (pin "2") (pinfunction "2_2") (pintype "bidirectional"))
      (node (ref "C34") (pin "2") (pinfunction "2_2") (pintype "bidirectional"))
      (node (ref "C35") (pin "2") (pinfunction "2_2") (pintype "bidirectional"))
      (node (ref "C36") (pin "2") (pinfunction "2_2") (pintype "bidirectional"))
      (node (ref "C37") (pin "P$1") (pinfunction "P$1_P$1") (pintype "bidirectional"))
      (node (ref "C4") (pin "P$2") (pinfunction "P$2_P$2") (pintype "bidirectional"))
      (node (ref "C40") (pin "1") (pinfunction "1_1") (pintype "bidirectional"))
      (node (ref "C41") (pin "2") (pinfunction "2_2") (pintype "bidirectional"))
      (node (ref "C42") (pin "2") (pinfunction "2_2") (pintype "bidirectional"))
      (node (ref "C43") (pin "P$2") (pinfunction "P$2_P$2") (pintype "bidirectional"))
      (node (ref "C44") (pin "2") (pinfunction "2_2") (pintype "bidirectional"))
      (node (ref "C45") (pin "1") (pinfunction "1_1") (pintype "bidirectional"))
      (node (ref "C46") (pin "2") (pinfunction "2_2") (pintype "bidirectional"))
      (node (ref "C47") (pin "1") (pinfunction "1_1") (pintype "bidirectional"))
      (node (ref "C48") (pin "2") (pinfunction "2_2") (pintype "bidirectional"))
      (node (ref "C49") (pin "2") (pinfunction "2_2") (pintype "bidirectional"))
      (node (ref "C5") (pin "P$1") (pinfunction "1_P$1") (pintype "bidirectional"))
      (node (ref "C50") (pin "1") (pinfunction "1_1") (pintype "bidirectional"))
      (node (ref "C53") (pin "2") (pinfunction "2_2") (pintype "bidirectional"))
      (node (ref "C54") (pin "P$1") (pinfunction "P$1_P$1") (pintype "bidirectional"))
      (node (ref "C55") (pin "P$2") (pinfunction "P$2_P$2") (pintype "bidirectional"))
      (node (ref "C56") (pin "2") (pinfunction "2_2") (pintype "bidirectional"))
      (node (ref "C57") (pin "2") (pinfunction "2_2") (pintype "bidirectional"))
      (node (ref "C58") (pin "P$2") (pinfunction "2_P$2") (pintype "bidirectional"))
      (node (ref "C59") (pin "P$2") (pinfunction "2_P$2") (pintype "bidirectional"))
      (node (ref "C6") (pin "P$1") (pinfunction "1_P$1") (pintype "bidirectional"))
      (node (ref "C60") (pin "P$2") (pinfunction "2_P$2") (pintype "bidirectional"))
      (node (ref "C61") (pin "P$2") (pinfunction "2_P$2") (pintype "bidirectional"))
      (node (ref "C62") (pin "P$2") (pinfunction "2_P$2") (pintype "bidirectional"))
      (node (ref "C63") (pin "P$2") (pinfunction "2_P$2") (pintype "bidirectional"))
      (node (ref "C64") (pin "P$2") (pinfunction "2_P$2") (pintype "bidirectional"))
      (node (ref "C65") (pin "P$2") (pinfunction "2_P$2") (pintype "bidirectional"))
      (node (ref "C66") (pin "P$2") (pinfunction "2_P$2") (pintype "bidirectional"))
      (node (ref "C67") (pin "P$2") (pinfunction "2_P$2") (pintype "bidirectional"))
      (node (ref "C69") (pin "2") (pinfunction "2_2") (pintype "bidirectional"))
      (node (ref "C70") (pin "P$2") (pinfunction "2_P$2") (pintype "bidirectional"))
      (node (ref "C71") (pin "P$1") (pinfunction "1_P$1") (pintype "bidirectional"))
      (node (ref "C72") (pin "P$2") (pinfunction "2_P$2") (pintype "bidirectional"))
      (node (ref "C73") (pin "P$2") (pinfunction "2_P$2") (pintype "bidirectional"))
      (node (ref "C74") (pin "P$2") (pinfunction "2_P$2") (pintype "bidirectional"))
      (node (ref "C76") (pin "2") (pinfunction "2_2") (pintype "passive"))
      (node (ref "C77") (pin "P$2") (pinfunction "2_P$2") (pintype "bidirectional"))
      (node (ref "C78") (pin "P$2") (pinfunction "2_P$2") (pintype "bidirectional"))
      (node (ref "C79") (pin "P$1") (pinfunction "1_P$1") (pintype "bidirectional"))
      (node (ref "C80") (pin "2") (pinfunction "2_2") (pintype "passive"))
      (node (ref "C81") (pin "2") (pinfunction "2_2") (pintype "passive"))
      (node (ref "C90") (pin "P$2") (pinfunction "2_P$2") (pintype "bidirectional"))
      (node (ref "C91") (pin "P$2") (pinfunction "2_P$2") (pintype "bidirectional"))
      (node (ref "CX1") (pin "2") (pinfunction "2_2") (pintype "bidirectional"))
      (node (ref "CX2") (pin "2") (pinfunction "2_2") (pintype "bidirectional"))
      (node (ref "CX3") (pin "2") (pinfunction "2_2") (pintype "passive"))
      (node (ref "CX4") (pin "2") (pinfunction "2_2") (pintype "passive"))
      (node (ref "D3") (pin "2") (pinfunction "A_2") (pintype "passive"))
      (node (ref "J1") (pin "5") (pinfunction "GND_5") (pintype "bidirectional"))
      (node (ref "J1") (pin "B5") (pinfunction "GND_B5") (pintype "bidirectional"))
      (node (ref "J2") (pin "5") (pinfunction "GND_5") (pintype "bidirectional"))
      (node (ref "J2") (pin "B5") (pinfunction "GND_B5") (pintype "bidirectional"))
      (node (ref "J4") (pin "1") (pinfunction "1_1") (pintype "bidirectional"))
      (node (ref "J4") (pin "1SUPP") (pinfunction "1_1SUPP") (pintype "bidirectional"))
      (node (ref "JP3") (pin "1") (pinfunction "1_1") (pintype "passive"))
      (node (ref "JP9") (pin "2") (pinfunction "2_2") (pintype "passive"))
      (node (ref "Q2") (pin "S") (pinfunction "S_S") (pintype "passive"))
      (node (ref "R1") (pin "2") (pinfunction "2_2") (pintype "passive"))
      (node (ref "R14") (pin "1") (pinfunction "1_1") (pintype "passive"))
      (node (ref "R15") (pin "1") (pinfunction "1_1") (pintype "passive"))
      (node (ref "R24") (pin "1") (pinfunction "1_1") (pintype "passive"))
      (node (ref "R25") (pin "2") (pinfunction "2_2") (pintype "passive"))
      (node (ref "R26") (pin "1") (pinfunction "1_1") (pintype "passive"))
      (node (ref "R27") (pin "1") (pinfunction "1_1") (pintype "passive"))
      (node (ref "R30") (pin "1") (pinfunction "1_1") (pintype "passive"))
      (node (ref "R6") (pin "2") (pinfunction "2_2") (pintype "passive"))
      (node (ref "RX7") (pin "1") (pinfunction "1_1") (pintype "passive"))
      (node (ref "RX9") (pin "1") (pinfunction "1_1") (pintype "passive"))
      (node (ref "RZ6") (pin "2") (pinfunction "2_2") (pintype "passive"))
      (node (ref "RZ7") (pin "2") (pinfunction "2_2") (pintype "passive"))
      (node (ref "RZ8") (pin "2") (pinfunction "2_2") (pintype "passive"))
      (node (ref "S2") (pin "10") (pinfunction "GND_10") (pintype "bidirectional"))
      (node (ref "S2") (pin "12") (pinfunction "GND_12") (pintype "bidirectional"))
      (node (ref "S2") (pin "2") (pinfunction "GND_2") (pintype "bidirectional"))
      (node (ref "S2") (pin "7") (pinfunction "GND_7") (pintype "bidirectional"))
      (node (ref "S2") (pin "8") (pinfunction "GND_8") (pintype "bidirectional"))
      (node (ref "S2") (pin "PAD") (pinfunction "GND_PAD") (pintype "bidirectional"))
      (node (ref "S3") (pin "6") (pinfunction "GND_6") (pintype "bidirectional"))
      (node (ref "S3") (pin "7") (pinfunction "GND_7") (pintype "bidirectional"))
      (node (ref "S3") (pin "PAD") (pinfunction "GND_PAD") (pintype "bidirectional"))
      (node (ref "S4") (pin "G1") (pinfunction "GND_G1") (pintype "bidirectional"))
      (node (ref "S4") (pin "G2") (pinfunction "GND_G2") (pintype "bidirectional"))
      (node (ref "U1") (pin "B12") (pinfunction "VSSAUDA_B12") (pintype "bidirectional"))
      (node (ref "U1") (pin "B2") (pinfunction "VSSP-BUCK_REGS_GND_B2") (pintype "bidirectional"))
      (node (ref "U1") (pin "B5") (pinfunction "VSSA-ANALOG_GND_B5") (pintype "bidirectional"))
      (node (ref "U1") (pin "D2") (pinfunction "VSS-DGND_FOR_VDDF_AND_PADS_D2") (pintype "bidirectional"))
      (node (ref "U1") (pin "E12") (pinfunction "VSSAUDD_E12") (pintype "bidirectional"))
      (node (ref "U1") (pin "H1") (pinfunction "VSSB-BLE_UNREG_GND_H1") (pintype "bidirectional"))
      (node (ref "U1") (pin "J10") (pinfunction "VSS18-MIPI_J10") (pintype "bidirectional"))
      (node (ref "U1") (pin "L1") (pinfunction "VSSVCO-BLECORE_GND_FOR_VCO_L1") (pintype "bidirectional"))
      (node (ref "U1") (pin "L2") (pinfunction "VSSS-HVSIMOBUCK_GND_L2") (pintype "bidirectional"))
      (node (ref "U1") (pin "L8") (pinfunction "VSSAUSB_L8") (pintype "bidirectional"))
      (node (ref "U2") (pin "A14") (pinfunction "VSS1_A14") (pintype "bidirectional"))
      (node (ref "U2") (pin "A2") (pinfunction "VSS_A2") (pintype "bidirectional"))
      (node (ref "U2") (pin "B11") (pinfunction "VSS1_B11") (pintype "bidirectional"))
      (node (ref "U2") (pin "B3") (pinfunction "VSS_B3") (pintype "bidirectional"))
      (node (ref "U2") (pin "C10") (pinfunction "VSS1_C10") (pintype "bidirectional"))
      (node (ref "U2") (pin "C12") (pinfunction "VSS3_C12") (pintype "bidirectional"))
      (node (ref "U2") (pin "C6") (pinfunction "VSS_C6") (pintype "bidirectional"))
      (node (ref "U2") (pin "C8") (pinfunction "VSS1_C8") (pintype "bidirectional"))
      (node (ref "U2") (pin "D11") (pinfunction "VSS2_D11") (pintype "bidirectional"))
      (node (ref "U2") (pin "D13") (pinfunction "VSS3_D13") (pintype "bidirectional"))
      (node (ref "U2") (pin "D5") (pinfunction "VSS_D5") (pintype "bidirectional"))
      (node (ref "U2") (pin "D7") (pinfunction "VSS_D7") (pintype "bidirectional"))
      (node (ref "U2") (pin "D9") (pinfunction "VSS1_D9") (pintype "bidirectional"))
      (node (ref "U2") (pin "E10") (pinfunction "GND-RF_E10") (pintype "bidirectional"))
      (node (ref "U2") (pin "E12") (pinfunction "GND-RF_E12") (pintype "bidirectional"))
      (node (ref "U2") (pin "E14") (pinfunction "VSS2_E14") (pintype "bidirectional"))
      (node (ref "U2") (pin "E6") (pinfunction "GND-RF_E6") (pintype "bidirectional"))
      (node (ref "U2") (pin "F7") (pinfunction "GND-RF_F7") (pintype "bidirectional"))
      (node (ref "U2") (pin "F9") (pinfunction "GND-RF_F9") (pintype "bidirectional"))
      (node (ref "U2") (pin "G10") (pinfunction "GND-RF_G10") (pintype "bidirectional"))
      (node (ref "U2") (pin "G6") (pinfunction "GND-RF_G6") (pintype "bidirectional"))
      (node (ref "U2") (pin "H1") (pinfunction "GND-RF_H1") (pintype "bidirectional"))
      (node (ref "U2") (pin "H13") (pinfunction "GND-RF_H13") (pintype "bidirectional"))
      (node (ref "U2") (pin "H3") (pinfunction "GND-RF_H3") (pintype "bidirectional"))
      (node (ref "U2") (pin "H7") (pinfunction "GND-RF_H7") (pintype "bidirectional"))
      (node (ref "U2") (pin "H9") (pinfunction "GND-RF_H9") (pintype "bidirectional"))
      (node (ref "U3") (pin "3") (pinfunction "VSS_3") (pintype "bidirectional"))
      (node (ref "U3") (pin "7") (pinfunction "ISET2_7") (pintype "bidirectional"))
      (node (ref "U3") (pin "PAD") (pinfunction "VSS_PAD") (pintype "bidirectional"))
      (node (ref "U4") (pin "1") (pinfunction "PGND_1") (pintype "bidirectional"))
      (node (ref "U4") (pin "10") (pinfunction "EN1_10") (pintype "bidirectional"))
      (node (ref "U4") (pin "11") (pinfunction "EN2_11") (pintype "bidirectional"))
      (node (ref "U4") (pin "20") (pinfunction "PGND_20") (pintype "bidirectional"))
      (node (ref "U4") (pin "PAD") (pinfunction "PGND_PAD") (pintype "bidirectional"))
      (node (ref "U6") (pin "10") (pinfunction "CLKSEL0_10") (pintype "output"))
      (node (ref "U6") (pin "2") (pinfunction "GND_2") (pintype "bidirectional"))
      (node (ref "U6") (pin "25") (pinfunction "GNDIO_25") (pintype "bidirectional"))
      (node (ref "U7") (pin "3") (pinfunction "GND_3") (pintype "bidirectional"))
      (node (ref "U7") (pin "4") (pinfunction "GND_4") (pintype "bidirectional"))
      (node (ref "U7") (pin "5") (pinfunction "GND_5") (pintype "bidirectional"))
      (node (ref "U7") (pin "7") (pinfunction "GND_7") (pintype "bidirectional"))
      (node (ref "U7") (pin "9") (pinfunction "GND_9") (pintype "bidirectional"))
      (node (ref "U8") (pin "4") (pinfunction "GND_4") (pintype "bidirectional"))
      (node (ref "VR1") (pin "13") (pinfunction "GND2_13") (pintype "bidirectional"))
      (node (ref "VR1") (pin "3") (pinfunction "GND2_3") (pintype "bidirectional"))
      (node (ref "VR1") (pin "9") (pinfunction "GND1_9") (pintype "bidirectional"))
      (node (ref "VR2") (pin "2") (pinfunction "GND_2") (pintype "bidirectional"))
      (node (ref "VR2") (pin "PAD") (pinfunction "GND_PAD") (pintype "bidirectional"))
      (node (ref "VR3") (pin "2") (pinfunction "GND_2") (pintype "bidirectional"))
      (node (ref "VR3") (pin "PAD") (pinfunction "GND_PAD") (pintype "bidirectional"))
      (node (ref "X1") (pin "2") (pinfunction "GND_2") (pintype "bidirectional"))
      (node (ref "X1") (pin "4") (pinfunction "GND_4") (pintype "bidirectional"))
      (node (ref "X4") (pin "2") (pinfunction "GND_2") (pintype "bidirectional"))
      (node (ref "X4") (pin "4") (pinfunction "GND_4") (pintype "bidirectional"))
      (node (ref "XJ1") (pin "A1/B12") (pinfunction "GND_A1/B12") (pintype "power_in"))
      (node (ref "XJ1") (pin "B1/A12") (pinfunction "GND_B1/A12") (pintype "power_in"))
      (node (ref "XJ1") (pin "S1") (pinfunction "GND_S1") (pintype "power_in"))
      (node (ref "XJ1") (pin "S2") (pinfunction "GND_S2") (pintype "power_in"))
      (node (ref "XJ1") (pin "S3") (pinfunction "GND_S3") (pintype "power_in"))
      (node (ref "XJ1") (pin "S4") (pinfunction "GND_S4") (pintype "power_in"))
      (node (ref "XR16") (pin "2") (pinfunction "2_2") (pintype "passive"))
      (node (ref "XR17") (pin "2") (pinfunction "2_2") (pintype "passive"))
      (node (ref "XR19") (pin "1") (pinfunction "1_1") (pintype "passive"))
    )
    (net (code "67") (name "Net-(A4-ANTENNA)") (class "Default")
      (node (ref "A4") (pin "S1") (pinfunction "ANTENNA_S1") (pintype "bidirectional"))
      (node (ref "L8") (pin "2") (pinfunction "2_2") (pintype "passive"))
    )
    (net (code "68") (name "Net-(C1-Pad1)") (class "Default")
      (node (ref "C1") (pin "1") (pinfunction "1_1") (pintype "passive"))
      (node (ref "L7") (pin "2") (pinfunction "2_2") (pintype "passive"))
      (node (ref "L8") (pin "1") (pinfunction "1_1") (pintype "passive"))
    )
    (net (code "69") (name "Net-(C2-1)") (class "Default")
      (node (ref "C2") (pin "P$1") (pinfunction "1_P$1") (pintype "bidirectional"))
      (node (ref "U2") (pin "H11") (pinfunction "RF1_H11") (pintype "bidirectional"))
    )
    (net (code "70") (name "Net-(C2-2)") (class "Default")
      (node (ref "C2") (pin "P$2") (pinfunction "2_P$2") (pintype "bidirectional"))
      (node (ref "S2") (pin "11") (pinfunction "RFC_11") (pintype "bidirectional"))
    )
    (net (code "71") (name "Net-(C5-2)") (class "Default")
      (node (ref "C5") (pin "P$2") (pinfunction "2_P$2") (pintype "bidirectional"))
      (node (ref "U6") (pin "27") (pinfunction "XIN32_27") (pintype "bidirectional"))
      (node (ref "X2") (pin "2") (pinfunction "2_2") (pintype "bidirectional"))
    )
    (net (code "72") (name "Net-(C6-2)") (class "Default")
      (node (ref "C6") (pin "P$2") (pinfunction "2_P$2") (pintype "bidirectional"))
      (node (ref "U6") (pin "26") (pinfunction "XOUT32/CLKSEL1_26") (pintype "bidirectional"))
      (node (ref "X2") (pin "1") (pinfunction "1_1") (pintype "bidirectional"))
    )
    (net (code "73") (name "Net-(C7-2)") (class "Default")
      (node (ref "C7") (pin "P$2") (pinfunction "2_P$2") (pintype "bidirectional"))
      (node (ref "R26") (pin "2") (pinfunction "2_2") (pintype "passive"))
      (node (ref "R28") (pin "1") (pinfunction "1_1") (pintype "passive"))
      (node (ref "VR1") (pin "10") (pinfunction "FB2_10") (pintype "bidirectional"))
    )
    (net (code "74") (name "Net-(C8-1)") (class "Default")
      (node (ref "C8") (pin "P$1") (pinfunction "1_P$1") (pintype "bidirectional"))
      (node (ref "R27") (pin "2") (pinfunction "2_2") (pintype "passive"))
      (node (ref "R29") (pin "2") (pinfunction "2_2") (pintype "passive"))
      (node (ref "VR1") (pin "4") (pinfunction "FB1_4") (pintype "bidirectional"))
    )
    (net (code "75") (name "Net-(C58-1)") (class "Default")
      (node (ref "C58") (pin "P$1") (pinfunction "1_P$1") (pintype "bidirectional"))
      (node (ref "U1") (pin "C1") (pinfunction "VDDS-SRAM_HV_SUP_C1") (pintype "bidirectional"))
    )
    (net (code "76") (name "Net-(C59-1)") (class "Default")
      (node (ref "C59") (pin "P$1") (pinfunction "1_P$1") (pintype "bidirectional"))
      (node (ref "U1") (pin "A3") (pinfunction "VDDC-CORE_A3") (pintype "bidirectional"))
    )
    (net (code "77") (name "Net-(C60-1)") (class "Default")
      (node (ref "C60") (pin "P$1") (pinfunction "1_P$1") (pintype "bidirectional"))
      (node (ref "U1") (pin "B3") (pinfunction "VDDC_LV-CORE_LV_B3") (pintype "bidirectional"))
    )
    (net (code "78") (name "Net-(C71-2)") (class "Default")
      (node (ref "C71") (pin "P$2") (pinfunction "2_P$2") (pintype "bidirectional"))
      (node (ref "U1") (pin "B10") (pinfunction "LPMICBIAS_B10") (pintype "output"))
    )
    (net (code "79") (name "Net-(C78-1)") (class "Default")
      (node (ref "C78") (pin "P$1") (pinfunction "1_P$1") (pintype "bidirectional"))
      (node (ref "RZ11") (pin "1") (pinfunction "1_1") (pintype "passive"))
      (node (ref "VR2") (pin "1") (pinfunction "OUT_1") (pintype "power_in"))
    )
    (net (code "80") (name "Net-(C79-2)") (class "Default")
      (node (ref "C79") (pin "P$2") (pinfunction "2_P$2") (pintype "bidirectional"))
      (node (ref "U1") (pin "A12") (pinfunction "LPADC_VREF_A12") (pintype "bidirectional"))
    )
    (net (code "81") (name "Net-(C91-1)") (class "Default")
      (node (ref "C91") (pin "P$1") (pinfunction "1_P$1") (pintype "bidirectional"))
      (node (ref "RZ4") (pin "1") (pinfunction "1_1") (pintype "passive"))
      (node (ref "VR3") (pin "1") (pinfunction "OUT_1") (pintype "power_in"))
    )
    (net (code "82") (name "Net-(D1-PadA1)") (class "Default")
      (node (ref "D1") (pin "A1") (pinfunction "A1_A1") (pintype "bidirectional"))
      (node (ref "D1") (pin "A2") (pinfunction "A2_A2") (pintype "bidirectional"))
      (node (ref "D2") (pin "A1") (pinfunction "A1_A1") (pintype "bidirectional"))
      (node (ref "D2") (pin "A2") (pinfunction "A2_A2") (pintype "bidirectional"))
      (node (ref "JP1") (pin "1") (pinfunction "1_1") (pintype "passive"))
    )
    (net (code "83") (name "Net-(D1-PadC1)") (class "Default")
      (node (ref "D1") (pin "C1") (pinfunction "C1_C1") (pintype "bidirectional"))
      (node (ref "R5") (pin "1") (pinfunction "1_1") (pintype "passive"))
    )
    (net (code "84") (name "Net-(D1-PadC2)") (class "Default")
      (node (ref "D1") (pin "C2") (pinfunction "C2_C2") (pintype "bidirectional"))
      (node (ref "R2") (pin "1") (pinfunction "1_1") (pintype "passive"))
    )
    (net (code "85") (name "Net-(D2-PadC1)") (class "Default")
      (node (ref "D2") (pin "C1") (pinfunction "C1_C1") (pintype "bidirectional"))
      (node (ref "R4") (pin "1") (pinfunction "1_1") (pintype "passive"))
    )
    (net (code "86") (name "Net-(D2-PadC2)") (class "Default")
      (node (ref "D2") (pin "C2") (pinfunction "C2_C2") (pintype "bidirectional"))
      (node (ref "R3") (pin "1") (pinfunction "1_1") (pintype "passive"))
    )
    (net (code "87") (name "Net-(JP2-Pad1)") (class "Default")
      (node (ref "JP2") (pin "1") (pinfunction "1_1") (pintype "passive"))
      (node (ref "XR19") (pin "2") (pinfunction "2_2") (pintype "passive"))
    )
    (net (code "88") (name "Net-(L1-1)") (class "Default")
      (node (ref "L1") (pin "P$1") (pinfunction "1_P$1") (pintype "bidirectional"))
      (node (ref "VR1") (pin "2") (pinfunction "LX2_2") (pintype "bidirectional"))
    )
    (net (code "89") (name "Net-(L2-2)") (class "Default")
      (node (ref "L2") (pin "P$2") (pinfunction "2_P$2") (pintype "bidirectional"))
      (node (ref "VR1") (pin "8") (pinfunction "LX1_8") (pintype "bidirectional"))
    )
    (net (code "90") (name "Net-(L4-1)") (class "Default")
      (node (ref "C17") (pin "2") (pinfunction "2_2") (pintype "bidirectional"))
      (node (ref "C18") (pin "2") (pinfunction "2_2") (pintype "bidirectional"))
      (node (ref "C19") (pin "2") (pinfunction "2_2") (pintype "bidirectional"))
      (node (ref "L4") (pin "P$1") (pinfunction "1_P$1") (pintype "bidirectional"))
    )
    (net (code "91") (name "Net-(L4-2)") (class "Default")
      (node (ref "C10") (pin "2") (pinfunction "2_2") (pintype "bidirectional"))
      (node (ref "C16") (pin "2") (pinfunction "2_2") (pintype "bidirectional"))
      (node (ref "C21") (pin "2") (pinfunction "2_2") (pintype "bidirectional"))
      (node (ref "C39") (pin "2") (pinfunction "2_2") (pintype "bidirectional"))
      (node (ref "C9") (pin "2") (pinfunction "2_2") (pintype "bidirectional"))
      (node (ref "L4") (pin "P$2") (pinfunction "2_P$2") (pintype "bidirectional"))
      (node (ref "U4") (pin "19") (pinfunction "AC2_19") (pintype "bidirectional"))
    )
    (net (code "92") (name "Net-(L5-1)") (class "Default")
      (node (ref "L5") (pin "P$1") (pinfunction "1_P$1") (pintype "bidirectional"))
      (node (ref "U1") (pin "A1") (pinfunction "SIMOBUCK_SW_A1") (pintype "bidirectional"))
    )
    (net (code "93") (name "Net-(L5-2)") (class "Default")
      (node (ref "L5") (pin "P$2") (pinfunction "2_P$2") (pintype "bidirectional"))
      (node (ref "U1") (pin "A2") (pinfunction "SIMOBUCK_SWSEL_A2") (pintype "bidirectional"))
    )
    (net (code "94") (name "Net-(LS1-N)") (class "Default")
      (node (ref "D4") (pin "ANODE") (pinfunction "ANODE_ANODE") (pintype "bidirectional"))
      (node (ref "LS1") (pin "-") (pinfunction "N_-") (pintype "passive"))
      (node (ref "Q2") (pin "D") (pinfunction "D_D") (pintype "passive"))
    )
    (net (code "95") (name "Net-(R6-Pad1)") (class "Default")
      (node (ref "R6") (pin "1") (pinfunction "1_1") (pintype "passive"))
      (node (ref "R7") (pin "2") (pinfunction "2_2") (pintype "passive"))
    )
    (net (code "96") (name "Net-(R8-Pad2)") (class "Default")
      (node (ref "R8") (pin "2") (pinfunction "2_2") (pintype "passive"))
      (node (ref "R9") (pin "1") (pinfunction "1_1") (pintype "passive"))
    )
    (net (code "97") (name "Net-(R13-Pad1)") (class "Default")
      (node (ref "R13") (pin "1") (pinfunction "1_1") (pintype "passive"))
      (node (ref "R14") (pin "2") (pinfunction "2_2") (pintype "passive"))
    )
    (net (code "98") (name "Net-(R13-Pad2)") (class "Default")
      (node (ref "R13") (pin "2") (pinfunction "2_2") (pintype "passive"))
      (node (ref "RT1") (pin "1") (pinfunction "1_1") (pintype "passive"))
    )
    (net (code "99") (name "Net-(R18-Pad2)") (class "Default")
      (node (ref "R18") (pin "2") (pinfunction "2_2") (pintype "passive"))
      (node (ref "R23") (pin "1") (pinfunction "1_1") (pintype "passive"))
    )
    (net (code "100") (name "Net-(S3A-OUT)") (class "Default")
      (node (ref "C33") (pin "1") (pinfunction "1_1") (pintype "bidirectional"))
      (node (ref "RZ1") (pin "1") (pinfunction "1_1") (pintype "passive"))
      (node (ref "S3") (pin "8") (pinfunction "OUT_8") (pintype "bidirectional"))
    )
    (net (code "101") (name "Net-(S3B-OUT)") (class "Default")
      (node (ref "C25") (pin "1") (pinfunction "1_1") (pintype "bidirectional"))
      (node (ref "RZ2") (pin "1") (pinfunction "1_1") (pintype "passive"))
      (node (ref "S3") (pin "5") (pinfunction "OUT_5") (pintype "bidirectional"))
    )
    (net (code "102") (name "Net-(TP0-TESTPOINT)") (class "Default")
      (node (ref "TP0") (pin "P$1") (pinfunction "TESTPOINT_P$1") (pintype "bidirectional"))
      (node (ref "U2") (pin "C2") (pinfunction "GPIO0/RXOKLED_C2") (pintype "bidirectional"))
    )
    (net (code "103") (name "Net-(TP1-TESTPOINT)") (class "Default")
      (node (ref "TP1") (pin "P$1") (pinfunction "TESTPOINT_P$1") (pintype "bidirectional"))
      (node (ref "U2") (pin "D3") (pinfunction "GPIO1/SFDLED_D3") (pintype "bidirectional"))
    )
    (net (code "104") (name "Net-(TP2-TESTPOINT)") (class "Default")
      (node (ref "TP2") (pin "P$1") (pinfunction "TESTPOINT_P$1") (pintype "bidirectional"))
      (node (ref "U2") (pin "E4") (pinfunction "GPIO2/RXLED_E4") (pintype "bidirectional"))
    )
    (net (code "105") (name "Net-(TP3-TESTPOINT)") (class "Default")
      (node (ref "TP3") (pin "P$1") (pinfunction "TESTPOINT_P$1") (pintype "bidirectional"))
      (node (ref "U2") (pin "E2") (pinfunction "GPIO3/TXLED_E2") (pintype "bidirectional"))
    )
    (net (code "106") (name "Net-(TP4-TESTPOINT)") (class "Default")
      (node (ref "TP4") (pin "P$1") (pinfunction "TESTPOINT_P$1") (pintype "bidirectional"))
      (node (ref "U2") (pin "F1") (pinfunction "GPIO4/EXTPA_F1") (pintype "bidirectional"))
    )
    (net (code "107") (name "Net-(TP5-TESTPOINT)") (class "Default")
      (node (ref "TP5") (pin "P$1") (pinfunction "TESTPOINT_P$1") (pintype "bidirectional"))
      (node (ref "U2") (pin "D1") (pinfunction "GPIO5/EXTTXE/SPIPOL_D1") (pintype "bidirectional"))
    )
    (net (code "108") (name "Net-(U1-RFIOP)") (class "Default")
      (node (ref "CX5") (pin "1") (pinfunction "1_1") (pintype "passive"))
      (node (ref "L7") (pin "1") (pinfunction "1_1") (pintype "passive"))
      (node (ref "U1") (pin "M2") (pinfunction "RFIOP_M2") (pintype "bidirectional"))
    )
    (net (code "109") (name "Net-(U1-VDDBH_SW--BLE_BUCK_SW)") (class "Default")
      (node (ref "L6") (pin "1") (pinfunction "1_1") (pintype "bidirectional"))
      (node (ref "U1") (pin "H12") (pinfunction "VDDBH_SW--BLE_BUCK_SW_H12") (pintype "bidirectional"))
    )
    (net (code "110") (name "Net-(U1-XI)") (class "Default")
      (node (ref "C81") (pin "1") (pinfunction "1_1") (pintype "passive"))
      (node (ref "U1") (pin "A4") (pinfunction "XI_A4") (pintype "bidirectional"))
      (node (ref "X3") (pin "2") (pinfunction "2_2") (pintype "bidirectional"))
    )
    (net (code "111") (name "Net-(U1-XI32M)") (class "Default")
      (node (ref "CX4") (pin "1") (pinfunction "1_1") (pintype "passive"))
      (node (ref "U1") (pin "C12") (pinfunction "XI32M_C12") (pintype "bidirectional"))
      (node (ref "X1") (pin "3") (pinfunction "2_3") (pintype "bidirectional"))
    )
    (net (code "112") (name "Net-(U1-XO)") (class "Default")
      (node (ref "C80") (pin "1") (pinfunction "1_1") (pintype "passive"))
      (node (ref "U1") (pin "A5") (pinfunction "XO_A5") (pintype "bidirectional"))
      (node (ref "X3") (pin "1") (pinfunction "1_1") (pintype "bidirectional"))
    )
    (net (code "113") (name "Net-(U1-XO32M)") (class "Default")
      (node (ref "CX3") (pin "1") (pinfunction "1_1") (pintype "passive"))
      (node (ref "U1") (pin "D12") (pinfunction "XO32M_D12") (pintype "bidirectional"))
      (node (ref "X1") (pin "1") (pinfunction "1_1") (pintype "bidirectional"))
    )
    (net (code "114") (name "Net-(U2-RF2)") (class "Default")
      (node (ref "R1") (pin "1") (pinfunction "1_1") (pintype "passive"))
      (node (ref "U2") (pin "H5") (pinfunction "RF2_H5") (pintype "bidirectional"))
    )
    (net (code "115") (name "Net-(U2-VDD2A)") (class "Default")
      (node (ref "C12") (pin "P$1") (pinfunction "P$1_P$1") (pintype "bidirectional"))
      (node (ref "FB1") (pin "P$2") (pinfunction "P$2_P$2") (pintype "bidirectional"))
      (node (ref "U2") (pin "F15") (pinfunction "VDD2A_F15") (pintype "bidirectional"))
    )
    (net (code "116") (name "Net-(U2-VIO_D)") (class "Default")
      (node (ref "C23") (pin "1") (pinfunction "1_1") (pintype "bidirectional"))
      (node (ref "U2") (pin "A4") (pinfunction "VIO_D_A4") (pintype "bidirectional"))
    )
    (net (code "117") (name "Net-(U2-VTX_D)") (class "Default")
      (node (ref "C37") (pin "P$2") (pinfunction "P$2_P$2") (pintype "bidirectional"))
      (node (ref "U2") (pin "C14") (pinfunction "VTX_D_C14") (pintype "bidirectional"))
    )
    (net (code "118") (name "Net-(U2-XTI)") (class "Default")
      (node (ref "C3") (pin "P$1") (pinfunction "P$1_P$1") (pintype "bidirectional"))
      (node (ref "U2") (pin "H15") (pinfunction "XTI_H15") (pintype "bidirectional"))
      (node (ref "X4") (pin "1") (pinfunction "1_1") (pintype "bidirectional"))
    )
    (net (code "119") (name "Net-(U2-XTO)") (class "Default")
      (node (ref "C4") (pin "P$1") (pinfunction "P$1_P$1") (pintype "bidirectional"))
      (node (ref "U2") (pin "G14") (pinfunction "XTO_G14") (pintype "bidirectional"))
      (node (ref "X4") (pin "3") (pinfunction "2_3") (pintype "bidirectional"))
    )
    (net (code "120") (name "Net-(U3-ISET)") (class "Default")
      (node (ref "R15") (pin "2") (pinfunction "2_2") (pintype "passive"))
      (node (ref "U3") (pin "2") (pinfunction "ISET_2") (pintype "bidirectional"))
    )
    (net (code "121") (name "Net-(U3-PRETERM)") (class "Default")
      (node (ref "RX7") (pin "2") (pinfunction "2_2") (pintype "passive"))
      (node (ref "U3") (pin "4") (pinfunction "PRETERM_4") (pintype "bidirectional"))
    )
    (net (code "122") (name "Net-(U4-AC1)") (class "Default")
      (node (ref "C10") (pin "1") (pinfunction "1_1") (pintype "bidirectional"))
      (node (ref "C15") (pin "2") (pinfunction "2_2") (pintype "bidirectional"))
      (node (ref "C17") (pin "1") (pinfunction "1_1") (pintype "bidirectional"))
      (node (ref "C18") (pin "1") (pinfunction "1_1") (pintype "bidirectional"))
      (node (ref "C19") (pin "1") (pinfunction "1_1") (pintype "bidirectional"))
      (node (ref "C20") (pin "2") (pinfunction "2_2") (pintype "bidirectional"))
      (node (ref "C38") (pin "2") (pinfunction "2_2") (pintype "bidirectional"))
      (node (ref "C9") (pin "1") (pinfunction "1_1") (pintype "bidirectional"))
      (node (ref "U4") (pin "2") (pinfunction "AC1_2") (pintype "bidirectional"))
    )
    (net (code "123") (name "Net-(U4-BOOT1)") (class "Default")
      (node (ref "C15") (pin "1") (pinfunction "1_1") (pintype "bidirectional"))
      (node (ref "U4") (pin "3") (pinfunction "BOOT1_3") (pintype "bidirectional"))
    )
    (net (code "124") (name "Net-(U4-BOOT2)") (class "Default")
      (node (ref "C16") (pin "1") (pinfunction "1_1") (pintype "bidirectional"))
      (node (ref "U4") (pin "17") (pinfunction "BOOT2_17") (pintype "bidirectional"))
    )
    (net (code "125") (name "Net-(U4-CLAMP1)") (class "Default")
      (node (ref "C38") (pin "1") (pinfunction "1_1") (pintype "bidirectional"))
      (node (ref "U4") (pin "5") (pinfunction "CLAMP1_5") (pintype "bidirectional"))
    )
    (net (code "126") (name "Net-(U4-CLAMP2)") (class "Default")
      (node (ref "C39") (pin "1") (pinfunction "1_1") (pintype "bidirectional"))
      (node (ref "U4") (pin "16") (pinfunction "CLAMP2_16") (pintype "bidirectional"))
    )
    (net (code "127") (name "Net-(U4-COMM1)") (class "Default")
      (node (ref "C20") (pin "1") (pinfunction "1_1") (pintype "bidirectional"))
      (node (ref "U4") (pin "6") (pinfunction "COMM1_6") (pintype "bidirectional"))
    )
    (net (code "128") (name "Net-(U4-COMM2)") (class "Default")
      (node (ref "C21") (pin "1") (pinfunction "1_1") (pintype "bidirectional"))
      (node (ref "U4") (pin "15") (pinfunction "COMM2_15") (pintype "bidirectional"))
    )
    (net (code "129") (name "Net-(U4-FOD)") (class "Default")
      (node (ref "R23") (pin "2") (pinfunction "2_2") (pintype "passive"))
      (node (ref "R7") (pin "1") (pinfunction "1_1") (pintype "passive"))
      (node (ref "R9") (pin "2") (pinfunction "2_2") (pintype "passive"))
      (node (ref "U4") (pin "14") (pinfunction "FOD_14") (pintype "bidirectional"))
    )
    (net (code "130") (name "Net-(U4-ILIM)") (class "Default")
      (node (ref "R8") (pin "1") (pinfunction "1_1") (pintype "passive"))
      (node (ref "U4") (pin "12") (pinfunction "ILIM_12") (pintype "bidirectional"))
    )
    (net (code "131") (name "Net-(U4-RECT)") (class "Default")
      (node (ref "C28") (pin "1") (pinfunction "1_1") (pintype "bidirectional"))
      (node (ref "C56") (pin "1") (pinfunction "1_1") (pintype "bidirectional"))
      (node (ref "C57") (pin "1") (pinfunction "1_1") (pintype "bidirectional"))
      (node (ref "R18") (pin "1") (pinfunction "1_1") (pintype "passive"))
      (node (ref "U4") (pin "18") (pinfunction "RECT_18") (pintype "bidirectional"))
    )
    (net (code "132") (name "Net-(U6-CAP)") (class "Default")
      (node (ref "C36") (pin "1") (pinfunction "1_1") (pintype "bidirectional"))
      (node (ref "U6") (pin "9") (pinfunction "CAP_9") (pintype "bidirectional"))
    )
    (net (code "133") (name "Net-(U6-PS1)") (class "Default")
      (node (ref "RX9") (pin "2") (pinfunction "2_2") (pintype "passive"))
      (node (ref "RZ12") (pin "1") (pinfunction "1_1") (pintype "passive"))
      (node (ref "U6") (pin "5") (pinfunction "PS1_5") (pintype "input"))
    )
    (net (code "134") (name "Net-(U7-VCTRL)") (class "Default")
      (node (ref "JP3") (pin "2") (pinfunction "2_2") (pintype "passive"))
      (node (ref "U7") (pin "8") (pinfunction "VCTRL_8") (pintype "bidirectional"))
    )
    (net (code "135") (name "Net-(U7-VDD)") (class "Default")
      (node (ref "C11") (pin "P$1") (pinfunction "P$1_P$1") (pintype "bidirectional"))
      (node (ref "C43") (pin "P$1") (pinfunction "P$1_P$1") (pintype "bidirectional"))
      (node (ref "RZ4") (pin "2") (pinfunction "2_2") (pintype "passive"))
      (node (ref "U7") (pin "1") (pinfunction "VDD_1") (pintype "bidirectional"))
    )
    (net (code "136") (name "Net-(VR2-EN)") (class "Default")
      (node (ref "RZ10") (pin "2") (pinfunction "2_2") (pintype "passive"))
      (node (ref "VR2") (pin "3") (pinfunction "EN_3") (pintype "input"))
    )
    (net (code "137") (name "Net-(XJ1-CC1)") (class "Default")
      (node (ref "XJ1") (pin "A5") (pinfunction "CC1_A5") (pintype "bidirectional"))
      (node (ref "XR16") (pin "1") (pinfunction "1_1") (pintype "passive"))
    )
    (net (code "138") (name "Net-(XJ1-CC2)") (class "Default")
      (node (ref "XJ1") (pin "B5") (pinfunction "CC2_B5") (pintype "bidirectional"))
      (node (ref "XR17") (pin "1") (pinfunction "1_1") (pintype "passive"))
    )
    (net (code "139") (name "RF1") (class "Default")
      (node (ref "S2") (pin "9") (pinfunction "J2_9") (pintype "bidirectional"))
      (node (ref "U7") (pin "6") (pinfunction "LNA_OUT_6") (pintype "bidirectional"))
    )
    (net (code "140") (name "RF2") (class "Default")
      (node (ref "A2") (pin "FEED") (pinfunction "ANTENNA_FEED") (pintype "bidirectional"))
      (node (ref "S2") (pin "3") (pinfunction "J3_3") (pintype "bidirectional"))
    )
    (net (code "141") (name "RF3") (class "Default")
      (node (ref "A3") (pin "FEED") (pinfunction "ANTENNA_FEED") (pintype "bidirectional"))
      (node (ref "S2") (pin "1") (pinfunction "J1_1") (pintype "bidirectional"))
      (node (ref "S4") (pin "IN") (pinfunction "IN_IN") (pintype "bidirectional"))
      (node (ref "S4") (pin "OUT") (pinfunction "A_OUT") (pintype "bidirectional"))
    )
    (net (code "142") (name "VBAT") (class "Default")
      (node (ref "C42") (pin "1") (pinfunction "1_1") (pintype "bidirectional"))
      (node (ref "J4") (pin "3") (pinfunction "3_3") (pintype "bidirectional"))
      (node (ref "J4") (pin "3SUPP") (pinfunction "3_3SUPP") (pintype "bidirectional"))
      (node (ref "JP9") (pin "1") (pinfunction "1_1") (pintype "passive"))
      (node (ref "S1") (pin "2") (pinfunction "2_2") (pintype "passive"))
      (node (ref "U3") (pin "10") (pinfunction "OUT_10") (pintype "bidirectional"))
    )
    (net (code "143") (name "VBAT_SWITCHED") (class "Default")
      (node (ref "C45") (pin "2") (pinfunction "2_2") (pintype "bidirectional"))
      (node (ref "C48") (pin "1") (pinfunction "1_1") (pintype "bidirectional"))
      (node (ref "R31") (pin "2") (pinfunction "2_2") (pintype "passive"))
      (node (ref "R33") (pin "1") (pinfunction "1_1") (pintype "passive"))
      (node (ref "R34") (pin "1") (pinfunction "1_1") (pintype "passive"))
      (node (ref "S1") (pin "3") (pinfunction "3_3") (pintype "passive"))
      (node (ref "VR1") (pin "1") (pinfunction "VIN2_1") (pintype "bidirectional"))
      (node (ref "VR1") (pin "7") (pinfunction "VIN1_7") (pintype "bidirectional"))
    )
    (net (code "144") (name "VDDAUDA_1P8-CLEAN") (class "Default")
      (node (ref "C72") (pin "P$1") (pinfunction "1_P$1") (pintype "bidirectional"))
      (node (ref "RZ11") (pin "2") (pinfunction "2_2") (pintype "passive"))
      (node (ref "U1") (pin "B11") (pinfunction "VDDAUDA_B11") (pintype "bidirectional"))
    )
    (net (code "145") (name "VQI") (class "Default")
      (node (ref "C29") (pin "1") (pinfunction "1_1") (pintype "bidirectional"))
      (node (ref "C41") (pin "1") (pinfunction "1_1") (pintype "bidirectional"))
      (node (ref "C53") (pin "1") (pinfunction "1_1") (pintype "bidirectional"))
      (node (ref "Q1") (pin "A2") (pinfunction "D1_A2") (pintype "bidirectional"))
      (node (ref "Q1") (pin "A3") (pinfunction "D1_A3") (pintype "bidirectional"))
      (node (ref "Q1") (pin "B3") (pinfunction "D1_B3") (pintype "bidirectional"))
      (node (ref "U3") (pin "1") (pinfunction "IN_1") (pintype "bidirectional"))
      (node (ref "U4") (pin "4") (pinfunction "OUT_4") (pintype "bidirectional"))
    )
    (net (code "146") (name "VR1_1P8_EN") (class "Default")
      (node (ref "R34") (pin "2") (pinfunction "2_2") (pintype "passive"))
      (node (ref "VR1") (pin "6") (pinfunction "EN1_6") (pintype "bidirectional"))
    )
    (net (code "147") (name "VR1_2P5_EN") (class "Default")
      (node (ref "R33") (pin "2") (pinfunction "2_2") (pintype "passive"))
      (node (ref "VR1") (pin "12") (pinfunction "EN2_12") (pintype "bidirectional"))
    )
    (net (code "148") (name "VUSB") (class "Default")
      (node (ref "C40") (pin "2") (pinfunction "2_2") (pintype "bidirectional"))
      (node (ref "Q1") (pin "B2") (pinfunction "D2_B2") (pintype "bidirectional"))
      (node (ref "Q1") (pin "C2") (pinfunction "D2_C2") (pintype "bidirectional"))
      (node (ref "Q1") (pin "C3") (pinfunction "D2_C3") (pintype "bidirectional"))
      (node (ref "U4") (pin "9") (pinfunction "AD_9") (pintype "bidirectional"))
      (node (ref "XJ1") (pin "A4/B9") (pinfunction "VBUS_A4/B9") (pintype "power_in"))
      (node (ref "XJ1") (pin "B4/A9") (pinfunction "VBUS_B4/A9") (pintype "power_in"))
    )
    (net (code "149") (name "unconnected-(Q1-S-PadB1)") (class "Default")
      (node (ref "Q1") (pin "B1") (pinfunction "S_B1") (pintype "bidirectional"))
    )
    (net (code "150") (name "unconnected-(S1-Pad1)") (class "Default")
      (node (ref "S1") (pin "1") (pinfunction "1_1") (pintype "passive"))
    )
    (net (code "151") (name "unconnected-(U1-GPIO0-PadH3)") (class "Default")
      (node (ref "U1") (pin "H3") (pinfunction "GPIO0_H3") (pintype "bidirectional"))
    )
    (net (code "152") (name "unconnected-(U1-GPIO1-PadJ4)") (class "Default")
      (node (ref "U1") (pin "J4") (pinfunction "GPIO1_J4") (pintype "bidirectional"))
    )
    (net (code "153") (name "unconnected-(U1-GPIO2-PadK4)") (class "Default")
      (node (ref "U1") (pin "K4") (pinfunction "GPIO2_K4") (pintype "bidirectional"))
    )
    (net (code "154") (name "unconnected-(U1-GPIO4-PadM4)") (class "Default")
      (node (ref "U1") (pin "M4") (pinfunction "GPIO4_M4") (pintype "bidirectional"))
    )
    (net (code "155") (name "unconnected-(U1-GPIO5-PadH4)") (class "Default")
      (node (ref "U1") (pin "H4") (pinfunction "GPIO5_H4") (pintype "bidirectional"))
    )
    (net (code "156") (name "unconnected-(U1-GPIO7-PadJ6)") (class "Default")
      (node (ref "U1") (pin "J6") (pinfunction "GPIO7_J6") (pintype "bidirectional"))
    )
    (net (code "157") (name "unconnected-(U1-GPIO11-PadE4)") (class "Default")
      (node (ref "U1") (pin "E4") (pinfunction "GPIO11_E4") (pintype "bidirectional"))
    )
    (net (code "158") (name "unconnected-(U1-GPIO12-PadB4)") (class "Default")
      (node (ref "U1") (pin "B4") (pinfunction "GPIO12_B4") (pintype "bidirectional"))
    )
    (net (code "159") (name "unconnected-(U1-GPIO15-PadE5)") (class "Default")
      (node (ref "U1") (pin "E5") (pinfunction "GPIO15_E5") (pintype "bidirectional"))
    )
    (net (code "160") (name "unconnected-(U1-GPIO16-PadD7)") (class "Default")
      (node (ref "U1") (pin "D7") (pinfunction "GPIO16_D7") (pintype "bidirectional"))
    )
    (net (code "161") (name "unconnected-(U1-GPIO19-PadC3)") (class "Default")
      (node (ref "U1") (pin "C3") (pinfunction "GPIO19_C3") (pintype "bidirectional"))
    )
    (net (code "162") (name "unconnected-(U1-GPIO22-PadF3)") (class "Default")
      (node (ref "U1") (pin "F3") (pinfunction "GPIO22_F3") (pintype "bidirectional"))
    )
    (net (code "163") (name "unconnected-(U1-GPIO23-PadF2)") (class "Default")
      (node (ref "U1") (pin "F2") (pinfunction "GPIO23_F2") (pintype "bidirectional"))
    )
    (net (code "164") (name "unconnected-(U1-GPIO28-PadE3)") (class "Default")
      (node (ref "U1") (pin "E3") (pinfunction "GPIO28_E3") (pintype "bidirectional"))
    )
    (net (code "165") (name "unconnected-(U1-GPIO29-PadF4)") (class "Default")
      (node (ref "U1") (pin "F4") (pinfunction "GPIO29_F4") (pintype "bidirectional"))
    )
    (net (code "166") (name "unconnected-(U1-GPIO37-PadF11)") (class "Default")
      (node (ref "U1") (pin "F11") (pinfunction "GPIO37_F11") (pintype "bidirectional"))
    )
    (net (code "167") (name "unconnected-(U1-GPIO52-PadC10)") (class "Default")
      (node (ref "U1") (pin "C10") (pinfunction "GPIO52_C10") (pintype "bidirectional"))
    )
    (net (code "168") (name "unconnected-(U1-GPIO54-PadD10)") (class "Default")
      (node (ref "U1") (pin "D10") (pinfunction "GPIO54_D10") (pintype "bidirectional"))
    )
    (net (code "169") (name "unconnected-(U1-GPIO56-PadE10)") (class "Default")
      (node (ref "U1") (pin "E10") (pinfunction "GPIO56_E10") (pintype "bidirectional"))
    )
    (net (code "170") (name "unconnected-(U1-GPIO57-PadE9)") (class "Default")
      (node (ref "U1") (pin "E9") (pinfunction "GPIO57_E9") (pintype "bidirectional"))
    )
    (net (code "171") (name "unconnected-(U1-GPIO59-PadJ8)") (class "Default")
      (node (ref "U1") (pin "J8") (pinfunction "GPIO59_J8") (pintype "bidirectional"))
    )
    (net (code "172") (name "unconnected-(U1-GPIO61-PadK6)") (class "Default")
      (node (ref "U1") (pin "K6") (pinfunction "GPIO61_K6") (pintype "bidirectional"))
    )
    (net (code "173") (name "unconnected-(U1-GPIO62-PadL6)") (class "Default")
      (node (ref "U1") (pin "L6") (pinfunction "GPIO62_L6") (pintype "bidirectional"))
    )
    (net (code "174") (name "unconnected-(U1-GPIO64-PadB6)") (class "Default")
      (node (ref "U1") (pin "B6") (pinfunction "GPIO64_B6") (pintype "bidirectional"))
    )
    (net (code "175") (name "unconnected-(U1-GPIO67-PadC6)") (class "Default")
      (node (ref "U1") (pin "C6") (pinfunction "GPIO67_C6") (pintype "bidirectional"))
    )
    (net (code "176") (name "unconnected-(U1-GPIO68-PadB7)") (class "Default")
      (node (ref "U1") (pin "B7") (pinfunction "GPIO68_B7") (pintype "bidirectional"))
    )
    (net (code "177") (name "unconnected-(U1-GPIO70-PadC5)") (class "Default")
      (node (ref "U1") (pin "C5") (pinfunction "GPIO70_C5") (pintype "bidirectional"))
    )
    (net (code "178") (name "unconnected-(U1-GPIO71-PadC7)") (class "Default")
      (node (ref "U1") (pin "C7") (pinfunction "GPIO71_C7") (pintype "bidirectional"))
    )
    (net (code "179") (name "unconnected-(U1-GPIO73-PadD8)") (class "Default")
      (node (ref "U1") (pin "D8") (pinfunction "GPIO73_D8") (pintype "bidirectional"))
    )
    (net (code "180") (name "unconnected-(U1-GPIO74-PadG11)") (class "Default")
      (node (ref "U1") (pin "G11") (pinfunction "GPIO74_G11") (pintype "bidirectional"))
    )
    (net (code "181") (name "unconnected-(U1-GPIO75-PadH11)") (class "Default")
      (node (ref "U1") (pin "H11") (pinfunction "GPIO75_H11") (pintype "bidirectional"))
    )
    (net (code "182") (name "unconnected-(U1-GPIO76-PadJ11)") (class "Default")
      (node (ref "U1") (pin "J11") (pinfunction "GPIO76_J11") (pintype "bidirectional"))
    )
    (net (code "183") (name "unconnected-(U1-GPIO77-PadK11)") (class "Default")
      (node (ref "U1") (pin "K11") (pinfunction "GPIO77_K11") (pintype "bidirectional"))
    )
    (net (code "184") (name "unconnected-(U1-GPIO78-PadL11)") (class "Default")
      (node (ref "U1") (pin "L11") (pinfunction "GPIO78_L11") (pintype "bidirectional"))
    )
    (net (code "185") (name "unconnected-(U1-GPIO84-PadJ9)") (class "Default")
      (node (ref "U1") (pin "J9") (pinfunction "GPIO84_J9") (pintype "bidirectional"))
    )
    (net (code "186") (name "unconnected-(U1-GPIO85-PadH9)") (class "Default")
      (node (ref "U1") (pin "H9") (pinfunction "GPIO85_H9") (pintype "bidirectional"))
    )
    (net (code "187") (name "unconnected-(U1-GPIO86-PadG10)") (class "Default")
      (node (ref "U1") (pin "G10") (pinfunction "GPIO86_G10") (pintype "bidirectional"))
    )
    (net (code "188") (name "unconnected-(U1-GPIO87-PadG9)") (class "Default")
      (node (ref "U1") (pin "G9") (pinfunction "GPIO87_G9") (pintype "bidirectional"))
    )
    (net (code "189") (name "unconnected-(U1-GPIO89-PadF10)") (class "Default")
      (node (ref "U1") (pin "F10") (pinfunction "GPIO89_F10") (pintype "bidirectional"))
    )
    (net (code "190") (name "unconnected-(U1-GPIO90-PadJ2)") (class "Default")
      (node (ref "U1") (pin "J2") (pinfunction "GPIO90_J2") (pintype "bidirectional"))
    )
    (net (code "191") (name "unconnected-(U1-GPIO91-PadK2)") (class "Default")
      (node (ref "U1") (pin "K2") (pinfunction "GPIO91_K2") (pintype "bidirectional"))
    )
    (net (code "192") (name "unconnected-(U1-LPADC_D0NSE0-PadA10)") (class "Default")
      (node (ref "U1") (pin "A10") (pinfunction "LPADC_D0NSE0_A10") (pintype "input"))
    )
    (net (code "193") (name "unconnected-(U1-LPADC_D0PSE1-PadA11)") (class "Default")
      (node (ref "U1") (pin "A11") (pinfunction "LPADC_D0PSE1_A11") (pintype "input"))
    )
    (net (code "194") (name "unconnected-(U1-LPADC_D1NSE2-PadC11)") (class "Default")
      (node (ref "U1") (pin "C11") (pinfunction "LPADC_D1NSE2_C11") (pintype "input"))
    )
    (net (code "195") (name "unconnected-(U1-LPADC_D1PSE3-PadD11)") (class "Default")
      (node (ref "U1") (pin "D11") (pinfunction "LPADC_D1PSE3_D11") (pintype "input"))
    )
    (net (code "196") (name "unconnected-(U1-MIPI_CLKN-PadJ12)") (class "Default")
      (node (ref "U1") (pin "J12") (pinfunction "MIPI_CLKN_J12") (pintype "bidirectional"))
    )
    (net (code "197") (name "unconnected-(U1-MIPI_CLKP-PadK12)") (class "Default")
      (node (ref "U1") (pin "K12") (pinfunction "MIPI_CLKP_K12") (pintype "bidirectional"))
    )
    (net (code "198") (name "unconnected-(U1-MIPI_DON-PadL12)") (class "Default")
      (node (ref "U1") (pin "L12") (pinfunction "MIPI_DON_L12") (pintype "bidirectional"))
    )
    (net (code "199") (name "unconnected-(U1-MIPI_DOP-PadM12)") (class "Default")
      (node (ref "U1") (pin "M12") (pinfunction "MIPI_DOP_M12") (pintype "bidirectional"))
    )
    (net (code "200") (name "unconnected-(U1-TXEN-PadK1)") (class "Default")
      (node (ref "U1") (pin "K1") (pinfunction "TXEN_K1") (pintype "output"))
    )
    (net (code "201") (name "unconnected-(VR1-NC1-Pad5)") (class "Default")
      (node (ref "VR1") (pin "5") (pinfunction "NC1_5") (pintype "bidirectional"))
    )
    (net (code "202") (name "unconnected-(VR1-NC2-Pad11)") (class "Default")
      (node (ref "VR1") (pin "11") (pinfunction "NC2_11") (pintype "bidirectional"))
    )
    (net (code "203") (name "unconnected-(XJ1-SBU1-PadA8)") (class "Default")
      (node (ref "XJ1") (pin "A8") (pinfunction "SBU1_A8") (pintype "bidirectional"))
    )
    (net (code "204") (name "unconnected-(XJ1-SBU2-PadB8)") (class "Default")
      (node (ref "XJ1") (pin "B8") (pinfunction "SBU2_B8") (pintype "bidirectional"))
    )
    (net (code "205") (name "~{AD_EN}") (class "Default")
      (node (ref "Q1") (pin "A1") (pinfunction "G1_A1") (pintype "input"))
      (node (ref "Q1") (pin "C1") (pinfunction "G2_C1") (pintype "input"))
      (node (ref "U4") (pin "8") (pinfunction "~{AD-EN}_8") (pintype "bidirectional"))
    )
  )
)
